# mb_01.net
KiCad netlist of a schematic drawn in EAGLE
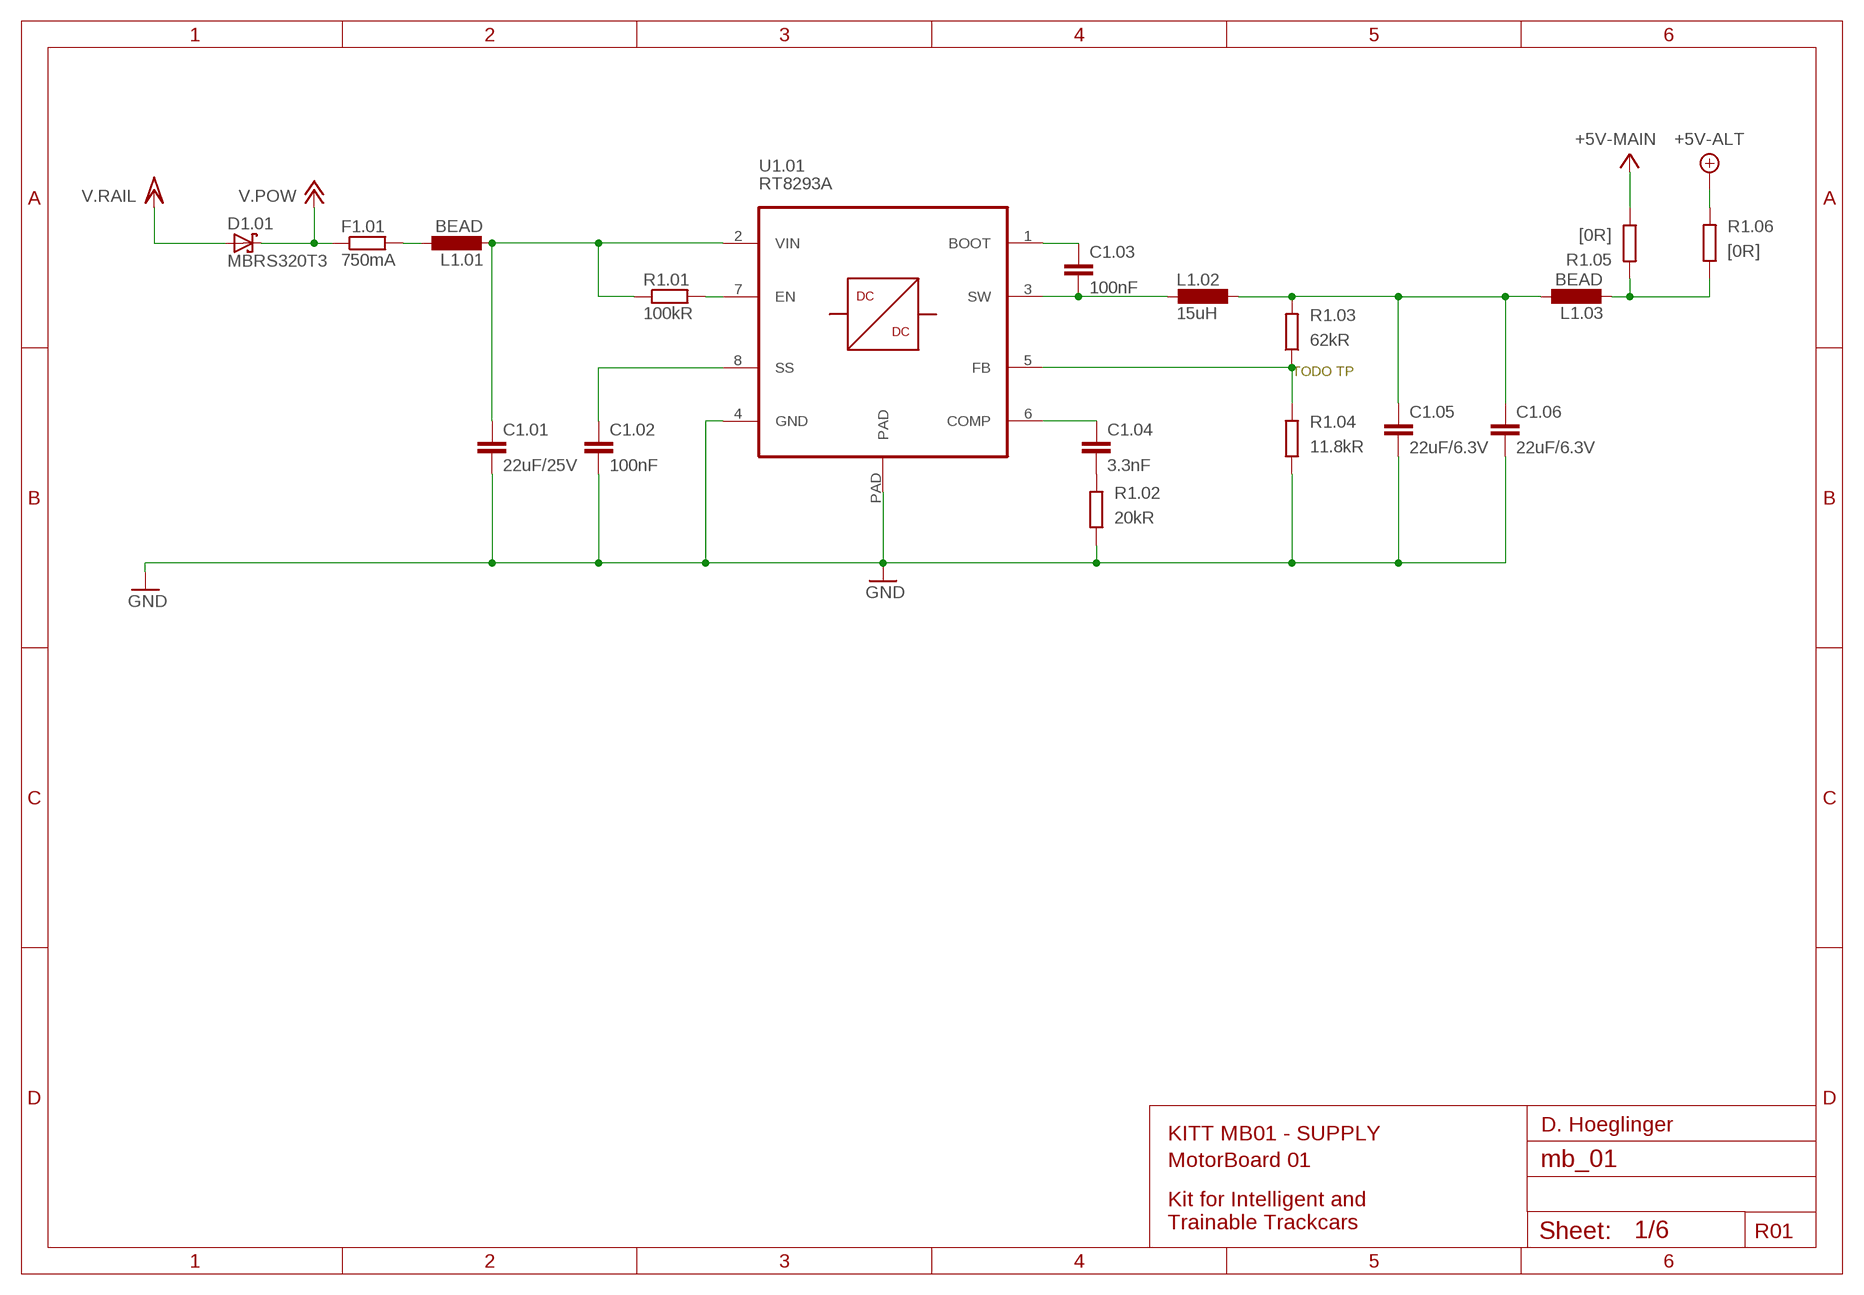
[diagram p0: schematic, sheet 1]
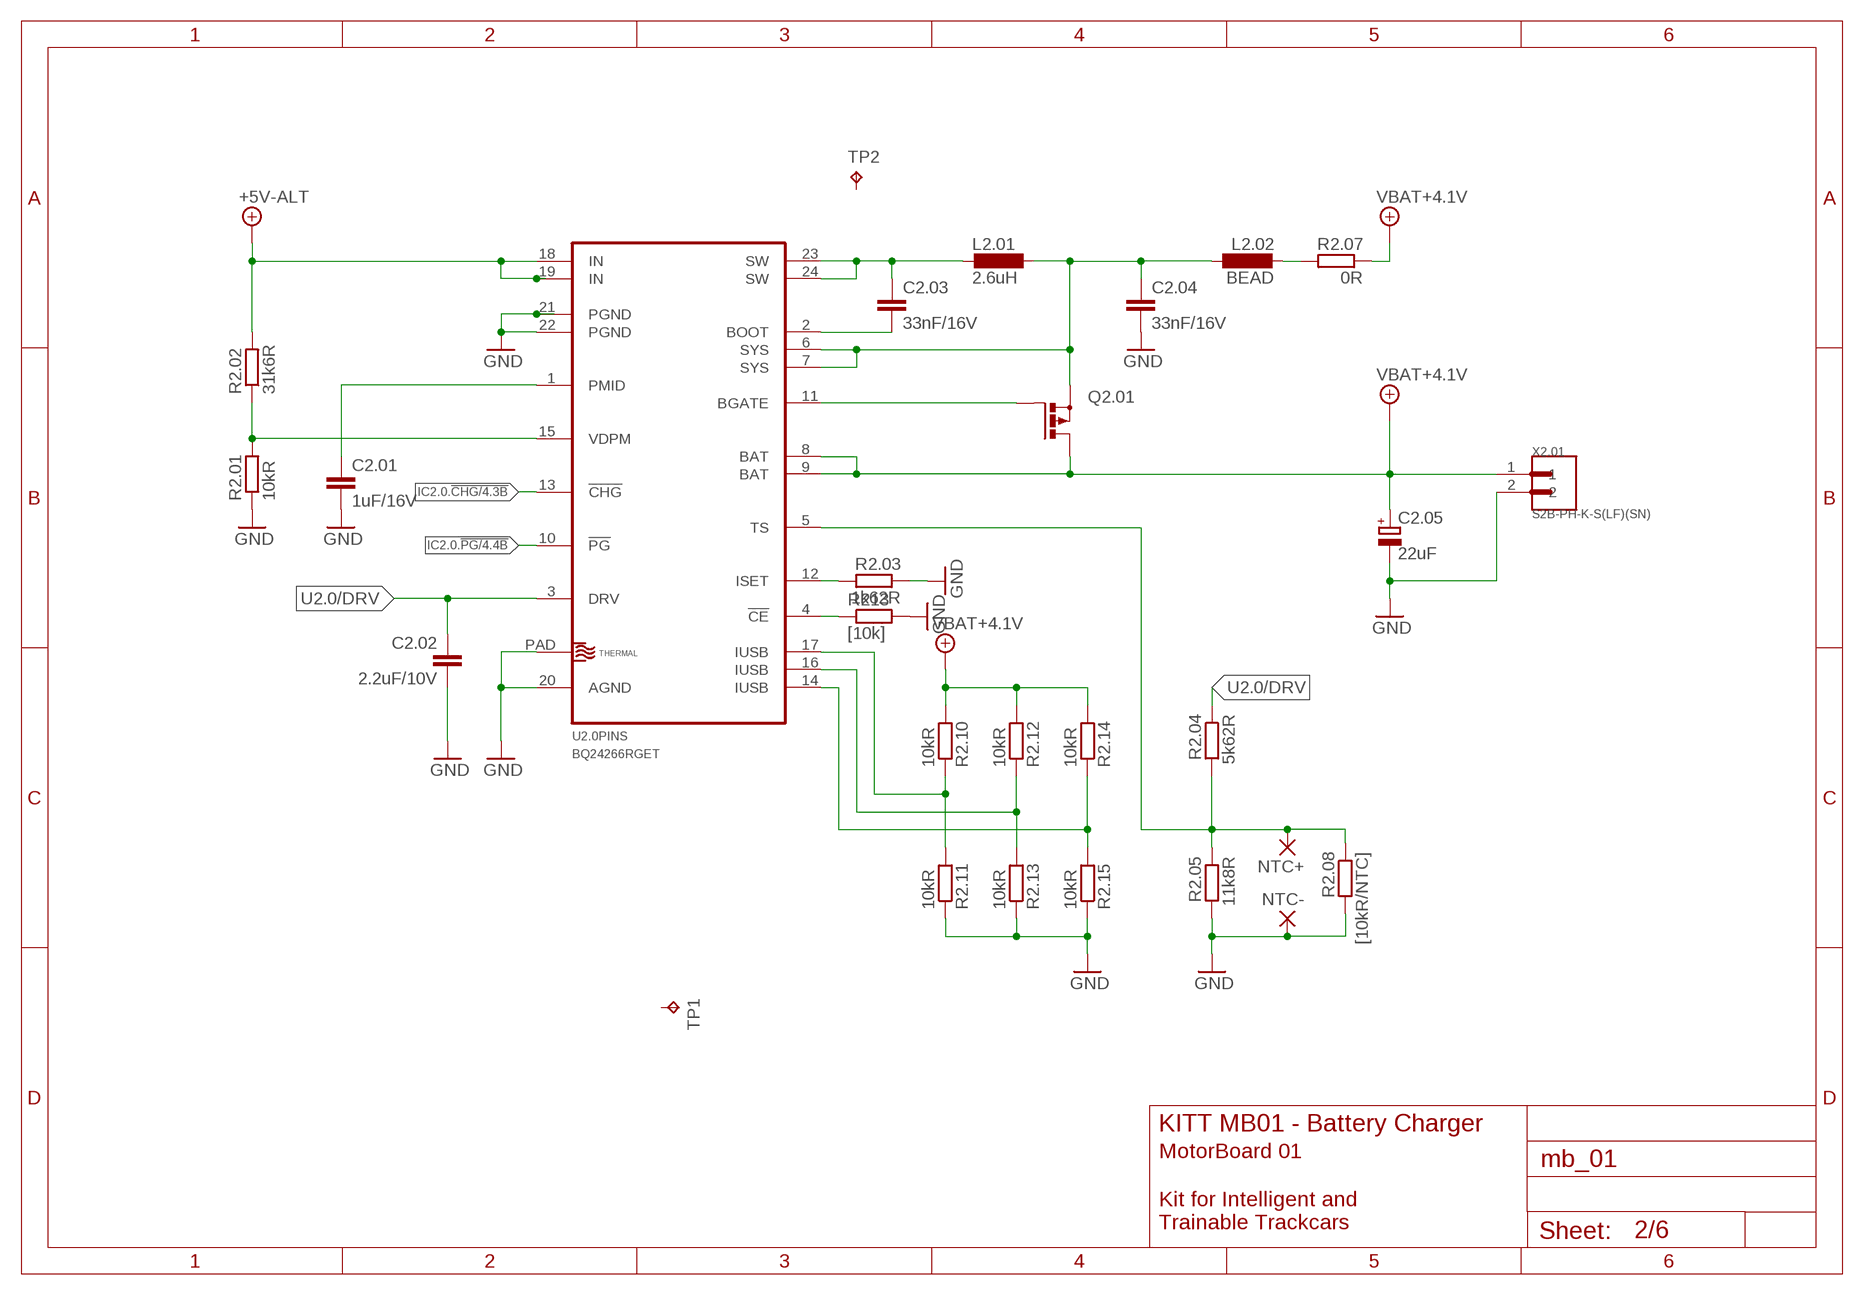
[diagram p1: schematic, sheet 2]
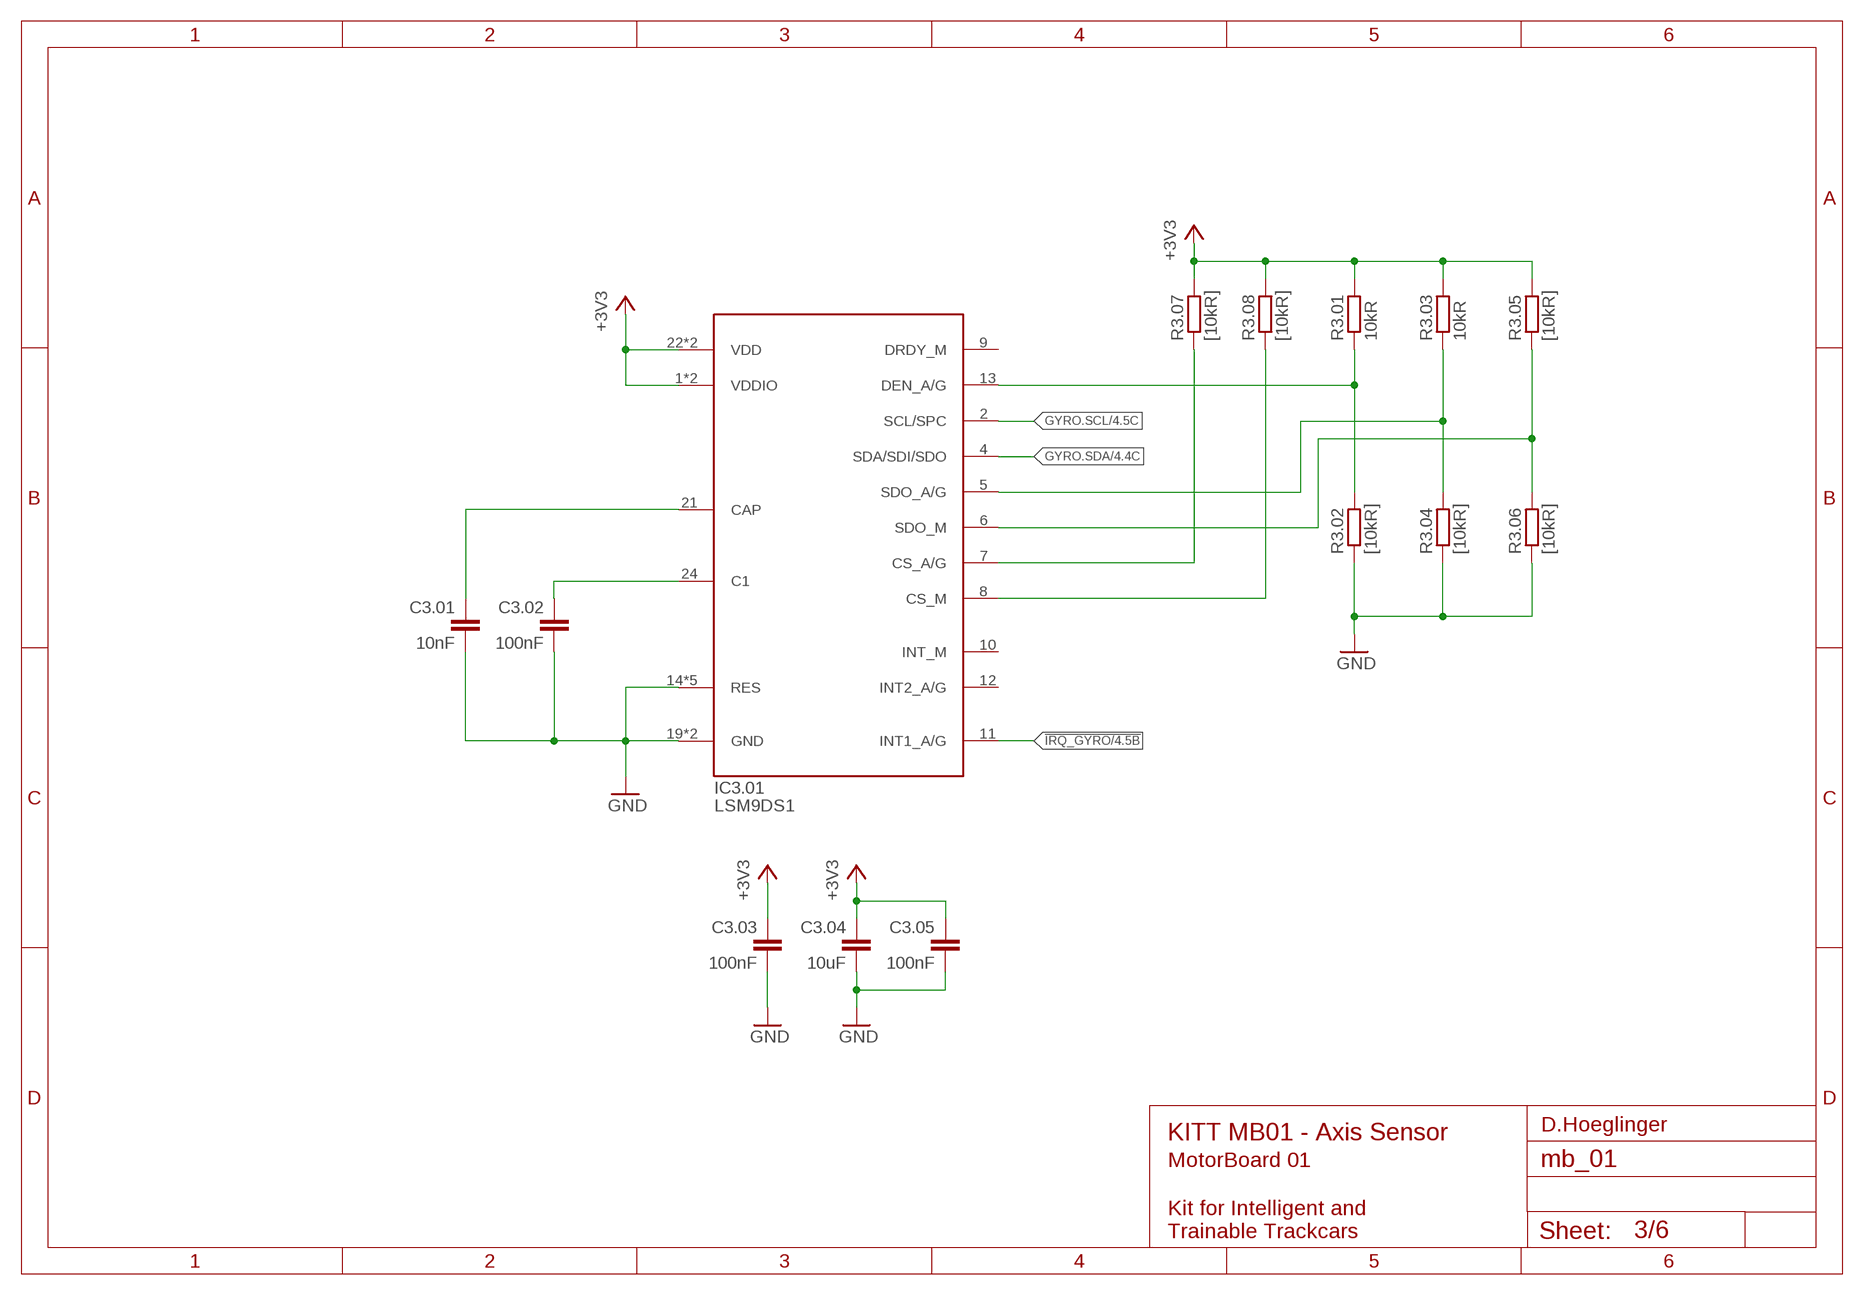
[diagram p2: schematic, sheet 3]
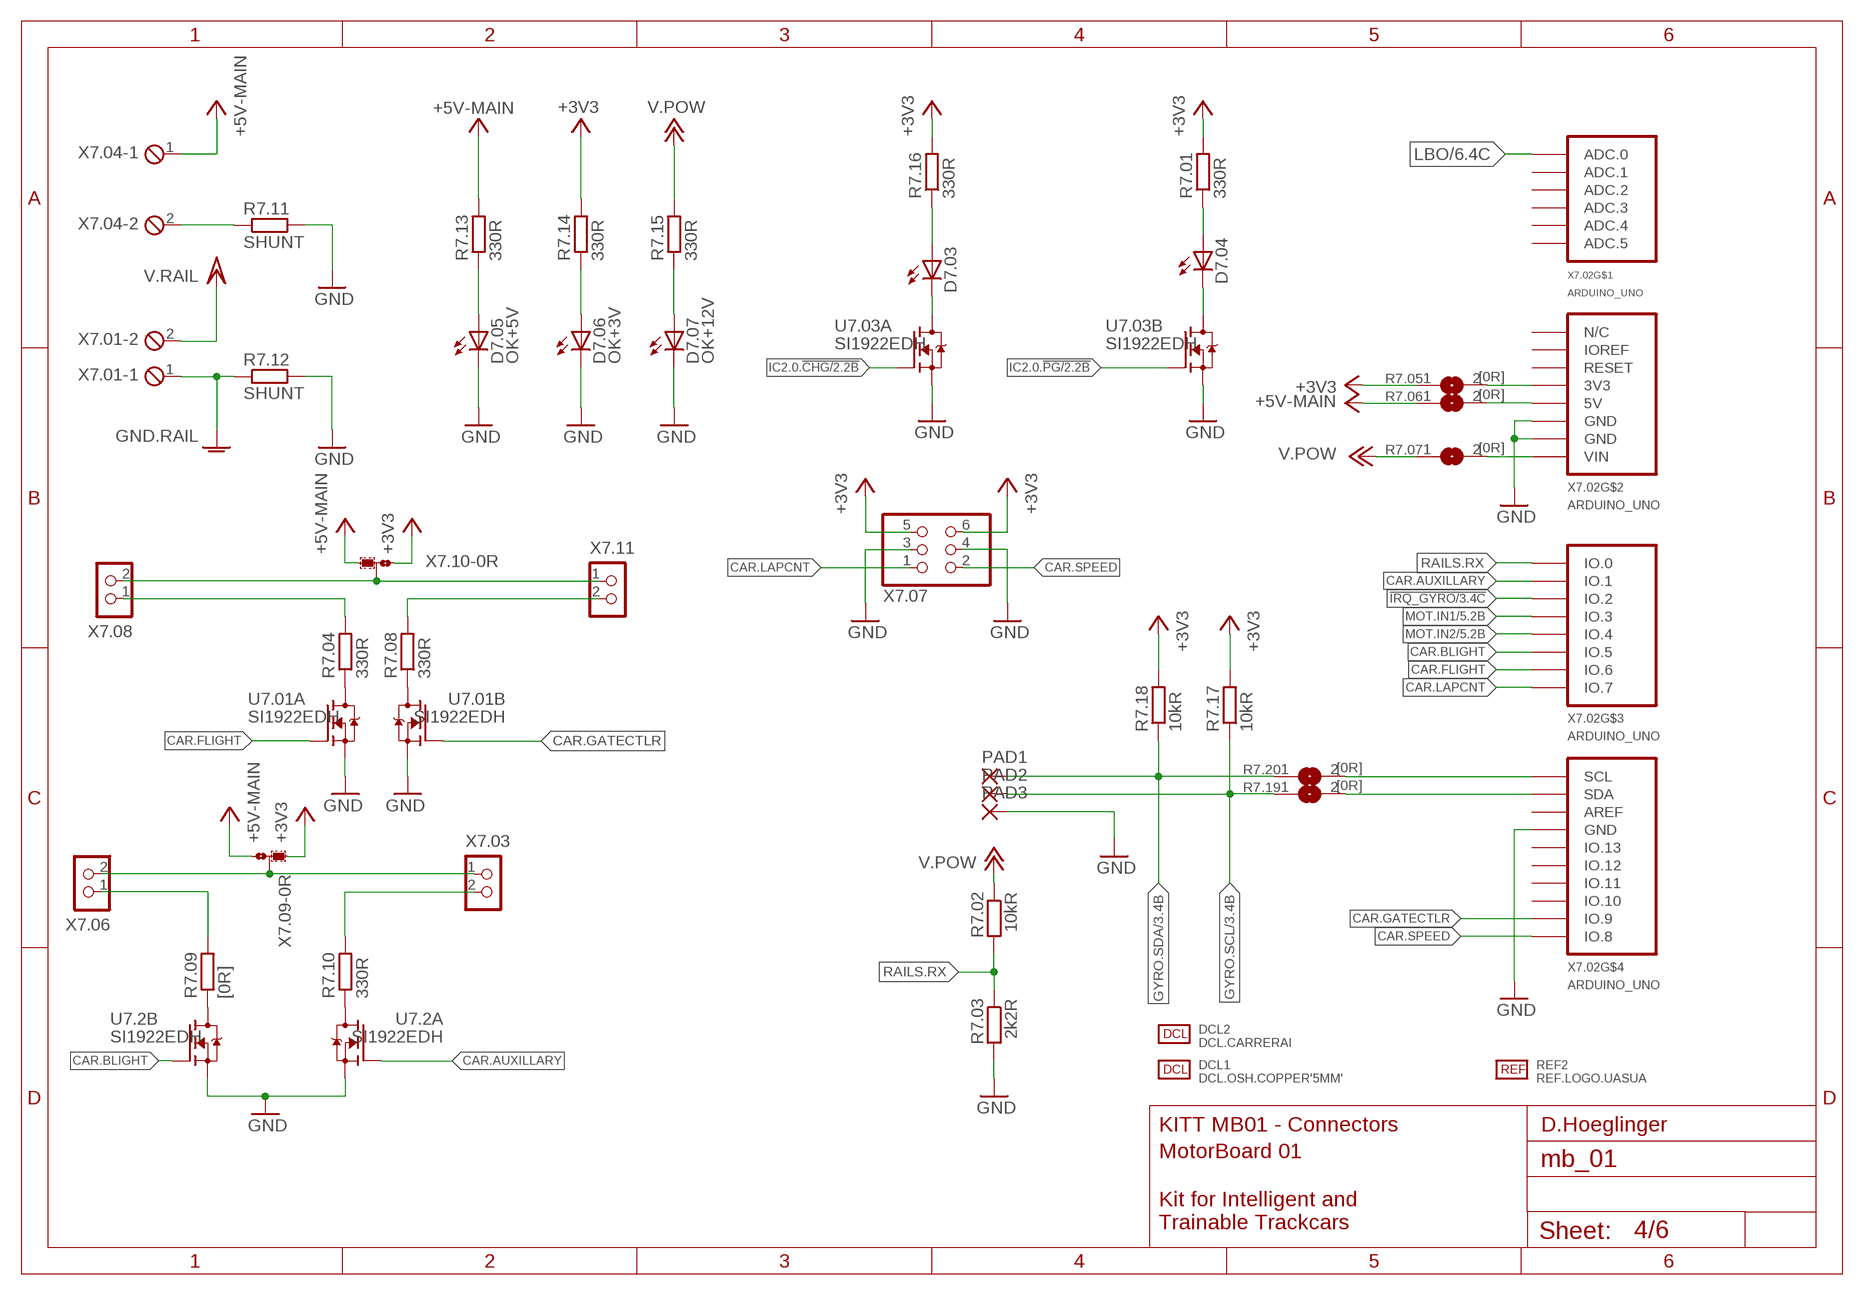
[diagram p3: schematic, sheet 4]
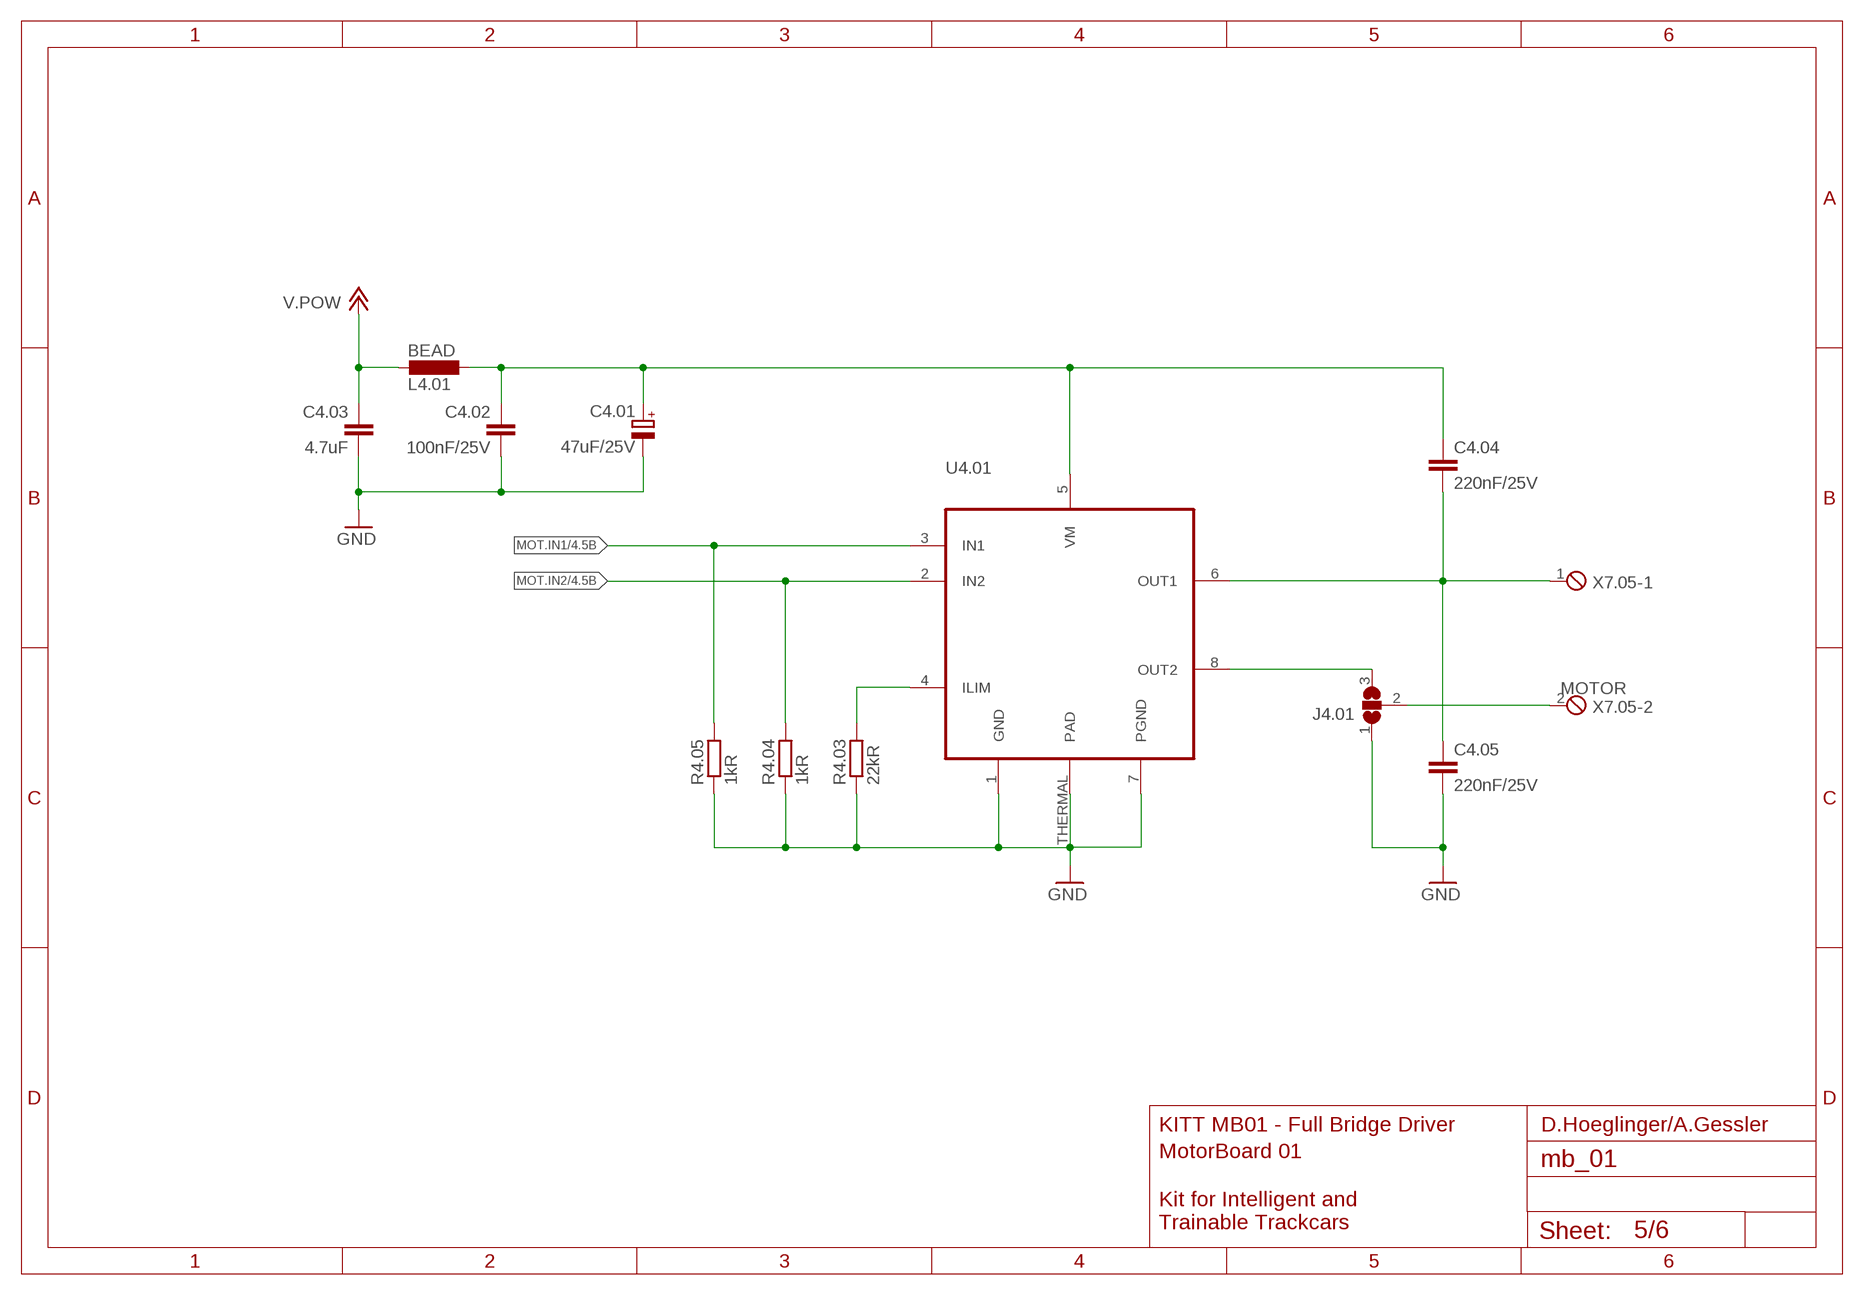
[diagram p4: schematic, sheet 5]
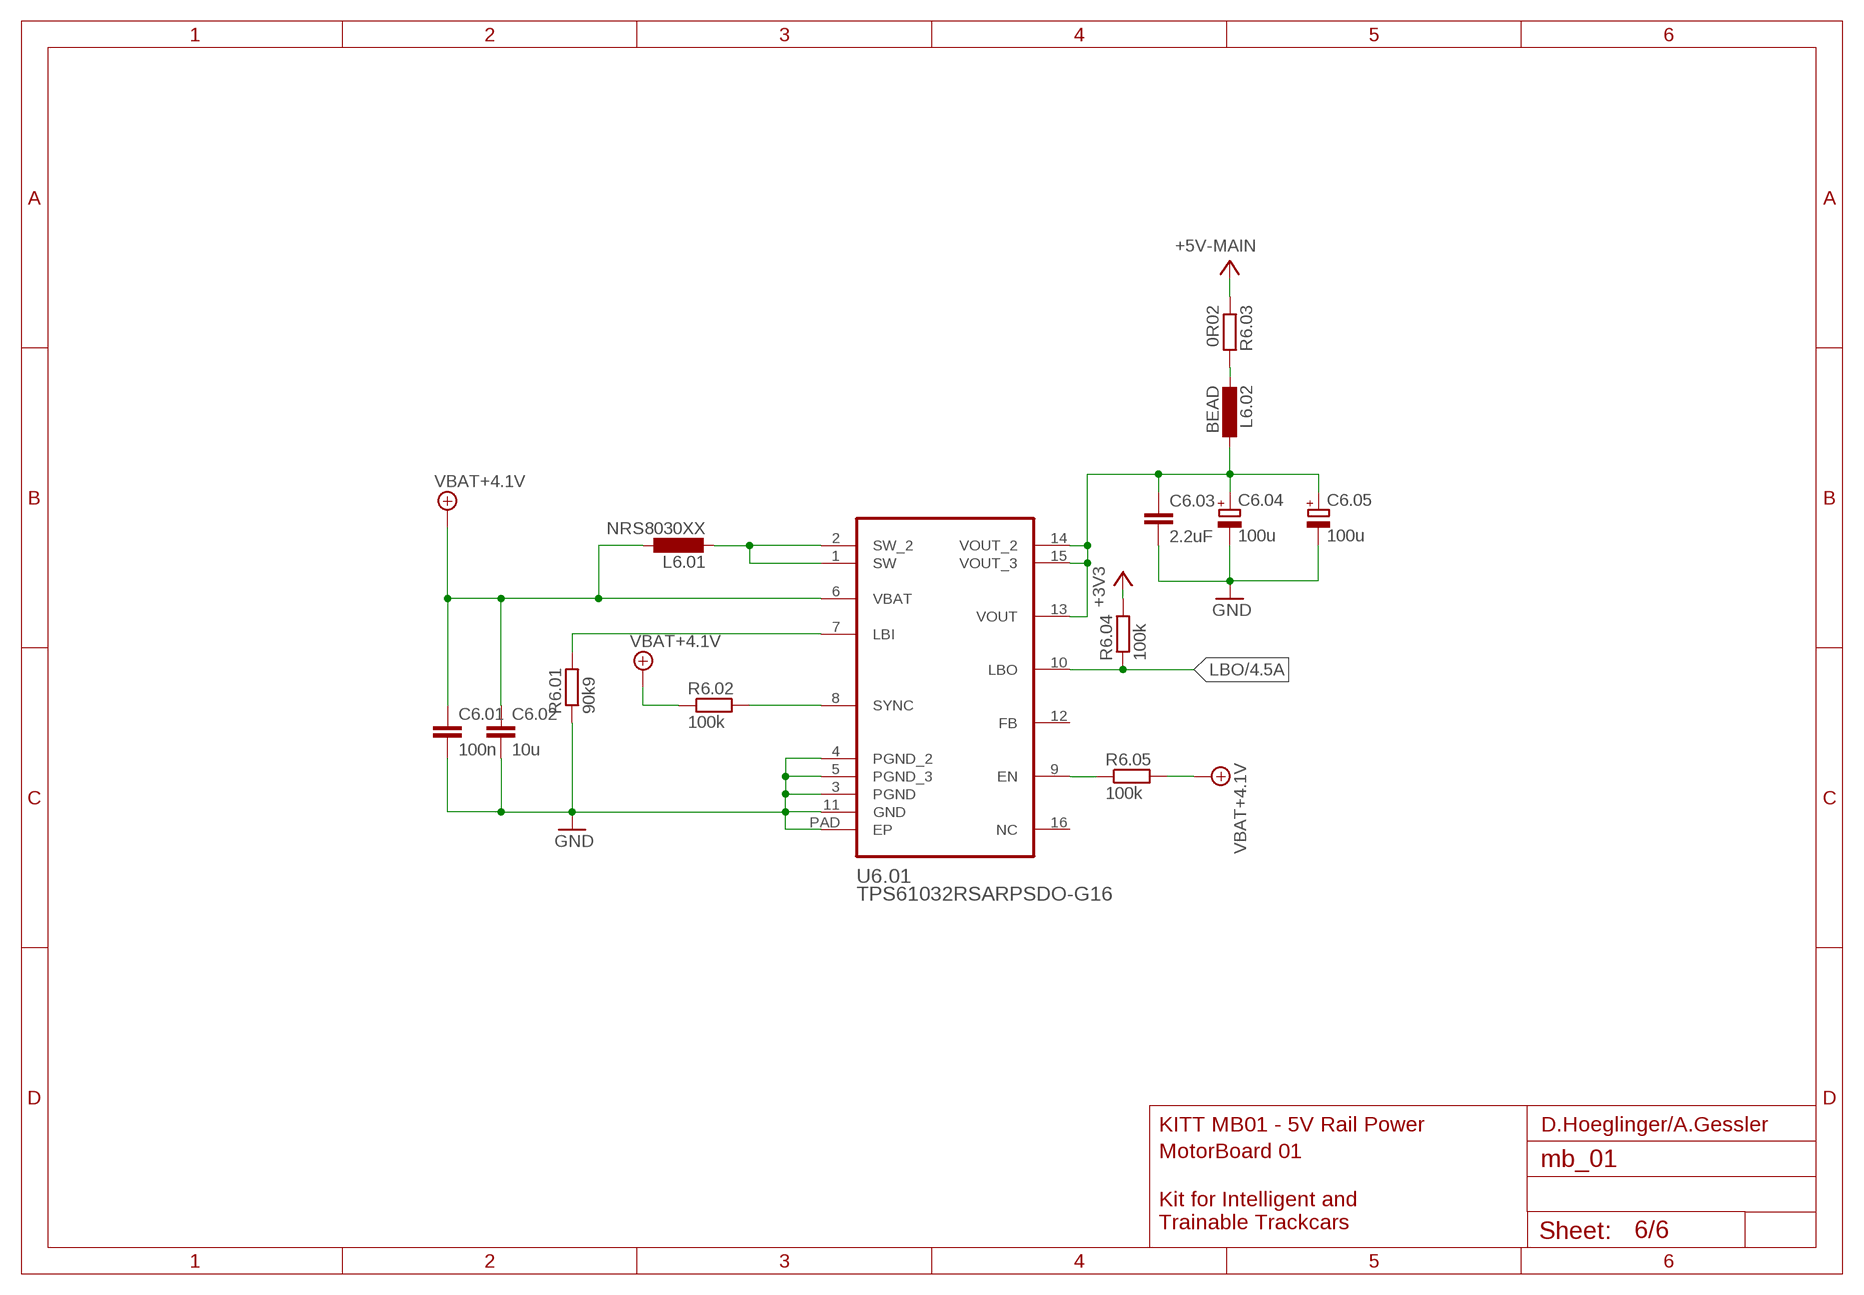
[diagram p5: schematic, sheet 6]

(export (version "E")
  (design (tool "Eeschema 10.0.6"))
  (components
    (comp (ref "C6.01")
      (value "100n")
      (footprint "eagle-import:C0402")
      (libsource (lib "eagle-import") (part "C-EUC0402"))
    )
    (comp (ref "C6.02")
      (value "10u")
      (footprint "eagle-import:C0603")
      (libsource (lib "eagle-import") (part "C-EUC0603"))
    )
    (comp (ref "C6.03")
      (value "2.2uF")
      (footprint "eagle-import:C0603")
      (libsource (lib "eagle-import") (part "C-EUC0603"))
    )
    (comp (ref "C6.04")
      (value "100u")
      (footprint "eagle-import:C-2312")
      (libsource (lib "eagle-import") (part "CPOL-29172312"))
    )
    (comp (ref "C6.05")
      (value "100u")
      (footprint "eagle-import:C-2312")
      (libsource (lib "eagle-import") (part "CPOL-29172312"))
    )
    (comp (ref "L6.01")
      (value "NRS8030XX")
      (footprint "eagle-import:TAIYO-YUDEN.NRS8030T4R7MJGJ")
      (libsource (lib "eagle-import") (part "NRS8030XX"))
    )
    (comp (ref "L6.02")
      (value "BEAD")
      (footprint "eagle-import:L4516C")
      (libsource (lib "eagle-import") (part "L-EUL4516C"))
    )
    (comp (ref "R6.01")
      (value "90k9")
      (footprint "eagle-import:R0402")
      (libsource (lib "eagle-import") (part "R-EU_R0402"))
    )
    (comp (ref "R6.02")
      (value "100k")
      (footprint "eagle-import:R0402")
      (libsource (lib "eagle-import") (part "R-EU_R0402"))
    )
    (comp (ref "R6.03")
      (value "0R02")
      (footprint "eagle-import:R0805")
      (libsource (lib "eagle-import") (part "R-EU_R0805"))
    )
    (comp (ref "R6.04")
      (value "100k")
      (footprint "eagle-import:R0402")
      (libsource (lib "eagle-import") (part "R-EU_R0402"))
    )
    (comp (ref "R6.05")
      (value "100k")
      (footprint "eagle-import:R0402")
      (libsource (lib "eagle-import") (part "R-EU_R0402"))
    )
    (comp (ref "U6.01")
      (value "TPS61032RSARPSDO-G16")
      (footprint "eagle-import:R-PDSO-G16")
      (libsource (lib "eagle-import") (part "TPS61032RSARPSDO-G16"))
    )
    (comp (ref "D7.03")
      (value "LEDCHIPLED_1206")
      (footprint "eagle-import:CHIPLED_1206")
      (libsource (lib "eagle-import") (part "LEDCHIPLED_1206"))
    )
    (comp (ref "D7.04")
      (value "LEDCHIPLED_1206")
      (footprint "eagle-import:CHIPLED_1206")
      (libsource (lib "eagle-import") (part "LEDCHIPLED_1206"))
    )
    (comp (ref "D7.05")
      (value "OK+5V")
      (footprint "eagle-import:CHIPLED_1206")
      (libsource (lib "eagle-import") (part "LEDCHIPLED_1206"))
    )
    (comp (ref "D7.06")
      (value "OK+3V")
      (footprint "eagle-import:CHIPLED_1206")
      (libsource (lib "eagle-import") (part "LEDCHIPLED_1206"))
    )
    (comp (ref "D7.07")
      (value "OK+12V")
      (footprint "eagle-import:CHIPLED_1206")
      (libsource (lib "eagle-import") (part "LEDCHIPLED_1206"))
    )
    (comp (ref "DCL1")
      (value "DCL.OSH.COPPER'5MM'")
      (footprint "eagle-import:DCL.LOGO-OSH.5MM")
      (libsource (lib "eagle-import") (part "DCL.OSH.COPPER'5MM'"))
    )
    (comp (ref "DCL2")
      (value "DCL.CARRERAI")
      (footprint "eagle-import:DCL.LOGO-CARRERAI.W30MM")
      (libsource (lib "eagle-import") (part "DCL.CARRERAI"))
    )
    (comp (ref "PAD1")
      (value "SMD2")
      (footprint "eagle-import:SMD1,27-2,54")
      (libsource (lib "eagle-import") (part "SMD2"))
    )
    (comp (ref "PAD2")
      (value "SMD2")
      (footprint "eagle-import:SMD1,27-2,54")
      (libsource (lib "eagle-import") (part "SMD2"))
    )
    (comp (ref "PAD3")
      (value "SMD2")
      (footprint "eagle-import:SMD1,27-2,54")
      (libsource (lib "eagle-import") (part "SMD2"))
    )
    (comp (ref "R7.01")
      (value "330R")
      (footprint "eagle-import:R0603")
      (libsource (lib "eagle-import") (part "R-EU_R0603"))
    )
    (comp (ref "R7.02")
      (value "10kR")
      (footprint "eagle-import:M0805")
      (libsource (lib "eagle-import") (part "R-EU_M0805"))
    )
    (comp (ref "R7.03")
      (value "2k2R")
      (footprint "eagle-import:M0805")
      (libsource (lib "eagle-import") (part "R-EU_M0805"))
    )
    (comp (ref "R7.04")
      (value "330R")
      (footprint "eagle-import:R0603")
      (libsource (lib "eagle-import") (part "R-EU_R0603"))
    )
    (comp (ref "R7.05")
      (value "[0R]")
      (footprint "eagle-import:SJ")
      (libsource (lib "eagle-import") (part "SJ"))
    )
    (comp (ref "R7.06")
      (value "[0R]")
      (footprint "eagle-import:SJ")
      (libsource (lib "eagle-import") (part "SJ"))
    )
    (comp (ref "R7.07")
      (value "[0R]")
      (footprint "eagle-import:SJ")
      (libsource (lib "eagle-import") (part "SJ"))
    )
    (comp (ref "R7.08")
      (value "330R")
      (footprint "eagle-import:R0603")
      (libsource (lib "eagle-import") (part "R-EU_R0603"))
    )
    (comp (ref "R7.09")
      (value "[0R]")
      (footprint "eagle-import:R0603")
      (libsource (lib "eagle-import") (part "R-EU_R0603"))
    )
    (comp (ref "R7.10")
      (value "330R")
      (footprint "eagle-import:R0603")
      (libsource (lib "eagle-import") (part "R-EU_R0603"))
    )
    (comp (ref "R7.11")
      (value "SHUNT")
      (footprint "eagle-import:R1206")
      (libsource (lib "eagle-import") (part "R-EU_R1206"))
    )
    (comp (ref "R7.12")
      (value "SHUNT")
      (footprint "eagle-import:R1206")
      (libsource (lib "eagle-import") (part "R-EU_R1206"))
    )
    (comp (ref "R7.13")
      (value "330R")
      (footprint "eagle-import:R0603")
      (libsource (lib "eagle-import") (part "R-EU_R0603"))
    )
    (comp (ref "R7.14")
      (value "330R")
      (footprint "eagle-import:R0603")
      (libsource (lib "eagle-import") (part "R-EU_R0603"))
    )
    (comp (ref "R7.15")
      (value "330R")
      (footprint "eagle-import:R0603")
      (libsource (lib "eagle-import") (part "R-EU_R0603"))
    )
    (comp (ref "R7.16")
      (value "330R")
      (footprint "eagle-import:R0603")
      (libsource (lib "eagle-import") (part "R-EU_R0603"))
    )
    (comp (ref "R7.17")
      (value "10kR")
      (footprint "eagle-import:R0402")
      (libsource (lib "eagle-import") (part "R-EU_R0402"))
    )
    (comp (ref "R7.18")
      (value "10kR")
      (footprint "eagle-import:R0402")
      (libsource (lib "eagle-import") (part "R-EU_R0402"))
    )
    (comp (ref "R7.19")
      (value "[0R]")
      (footprint "eagle-import:SJ")
      (libsource (lib "eagle-import") (part "SJ"))
    )
    (comp (ref "R7.20")
      (value "[0R]")
      (footprint "eagle-import:SJ")
      (libsource (lib "eagle-import") (part "SJ"))
    )
    (comp (ref "REF2")
      (value "REF.LOGO.UASUA")
      (footprint "eagle-import:REF_LOGO_UASUA")
      (libsource (lib "eagle-import") (part "REF.LOGO.UASUA"))
    )
    (comp (ref "U7.01")
      (value "SI1922EDH")
      (footprint "eagle-import:SC70-6")
      (libsource (lib "eagle-import") (part "SI1922EDH"))
    )
    (comp (ref "U7.2")
      (value "SI1922EDH")
      (footprint "eagle-import:SC70-6")
      (libsource (lib "eagle-import") (part "SI1922EDH"))
    )
    (comp (ref "U7.03")
      (value "SI1922EDH")
      (footprint "eagle-import:SC70-6")
      (libsource (lib "eagle-import") (part "SI1922EDH"))
    )
    (comp (ref "X7.01")
      (value "MPT2")
      (footprint "eagle-import:2POL254")
      (libsource (lib "eagle-import") (part "MPT2"))
    )
    (comp (ref "X7.02")
      (value "ARDUINO_UNO")
      (footprint "eagle-import:AU_PINS")
      (libsource (lib "eagle-import") (part "ARDUINO_UNO"))
    )
    (comp (ref "X7.03")
      (value "CON_HEADER_1X02")
      (footprint "eagle-import:M1X2_MALE_RIGHT_ANGLED_SMD")
      (libsource (lib "eagle-import") (part "CON_HEADER_1X02"))
    )
    (comp (ref "X7.04")
      (value "MPT2")
      (footprint "eagle-import:2POL254")
      (libsource (lib "eagle-import") (part "MPT2"))
    )
    (comp (ref "X7.06")
      (value "CON_HEADER_1X02")
      (footprint "eagle-import:M1X2_MALE_RIGHT_ANGLED_SMD")
      (libsource (lib "eagle-import") (part "CON_HEADER_1X02"))
    )
    (comp (ref "X7.07")
      (value "PINHD-2X3/90")
      (footprint "eagle-import:2X03_90")
      (libsource (lib "eagle-import") (part "PINHD-2X3/90"))
    )
    (comp (ref "X7.08")
      (value "CON_HEADER_1X02")
      (footprint "eagle-import:M1X2_MALE_RIGHT_ANGLED_SMD")
      (libsource (lib "eagle-import") (part "CON_HEADER_1X02"))
    )
    (comp (ref "X7.09")
      (value "0R-JUMPA")
      (footprint "eagle-import:A0R-JMP")
      (libsource (lib "eagle-import") (part "0R-JUMPA"))
    )
    (comp (ref "X7.10")
      (value "0R-JUMPA")
      (footprint "eagle-import:A0R-JMP")
      (libsource (lib "eagle-import") (part "0R-JUMPA"))
    )
    (comp (ref "X7.11")
      (value "CON_HEADER_1X02")
      (footprint "eagle-import:M1X2_MALE_RIGHT_ANGLED_SMD")
      (libsource (lib "eagle-import") (part "CON_HEADER_1X02"))
    )
    (comp (ref "C3.01")
      (value "10nF")
      (footprint "eagle-import:C0603")
      (libsource (lib "eagle-import") (part "C-EUC0603"))
    )
    (comp (ref "C3.02")
      (value "100nF")
      (footprint "eagle-import:C0402")
      (libsource (lib "eagle-import") (part "C-EUC0402"))
    )
    (comp (ref "C3.03")
      (value "100nF")
      (footprint "eagle-import:C0402")
      (libsource (lib "eagle-import") (part "C-EUC0402"))
    )
    (comp (ref "C3.04")
      (value "10uF")
      (footprint "eagle-import:C0603K")
      (libsource (lib "eagle-import") (part "resistor_C-EUC0603K"))
    )
    (comp (ref "C3.05")
      (value "100nF")
      (footprint "eagle-import:C0402")
      (libsource (lib "eagle-import") (part "C-EUC0402"))
    )
    (comp (ref "IC3.01")
      (value "LSM9DS1")
      (footprint "eagle-import:LGA-24")
      (fields (field (name "MF") "STMicroelectronics"))
      (libsource (lib "eagle-import") (part "LSM9DS1"))
    )
    (comp (ref "R3.01")
      (value "10kR")
      (footprint "eagle-import:R0402")
      (libsource (lib "eagle-import") (part "R-EU_R0402"))
    )
    (comp (ref "R3.02")
      (value "[10kR]")
      (footprint "eagle-import:R0402")
      (libsource (lib "eagle-import") (part "R-EU_R0402"))
    )
    (comp (ref "R3.03")
      (value "10kR")
      (footprint "eagle-import:R0402")
      (libsource (lib "eagle-import") (part "R-EU_R0402"))
    )
    (comp (ref "R3.04")
      (value "[10kR]")
      (footprint "eagle-import:R0402")
      (libsource (lib "eagle-import") (part "R-EU_R0402"))
    )
    (comp (ref "R3.05")
      (value "[10kR]")
      (footprint "eagle-import:R0402")
      (libsource (lib "eagle-import") (part "R-EU_R0402"))
    )
    (comp (ref "R3.06")
      (value "[10kR]")
      (footprint "eagle-import:R0402")
      (libsource (lib "eagle-import") (part "R-EU_R0402"))
    )
    (comp (ref "R3.07")
      (value "[10kR]")
      (footprint "eagle-import:R0402")
      (libsource (lib "eagle-import") (part "R-EU_R0402"))
    )
    (comp (ref "R3.08")
      (value "[10kR]")
      (footprint "eagle-import:R0402")
      (libsource (lib "eagle-import") (part "R-EU_R0402"))
    )
    (comp (ref "C2.01")
      (value "1uF/16V")
      (footprint "eagle-import:C0805")
      (libsource (lib "eagle-import") (part "C-EUC0805"))
    )
    (comp (ref "C2.02")
      (value "2.2uF/10V")
      (footprint "eagle-import:C0603K")
      (libsource (lib "eagle-import") (part "C-EUC0603K"))
    )
    (comp (ref "C2.03")
      (value "33nF/16V")
      (footprint "eagle-import:C0603")
      (libsource (lib "eagle-import") (part "C-EUC0603"))
    )
    (comp (ref "C2.04")
      (value "33nF/16V")
      (footprint "eagle-import:C0805")
      (libsource (lib "eagle-import") (part "C-EUC0805"))
    )
    (comp (ref "C2.05")
      (value "22uF")
      (footprint "eagle-import:A_3216-18R")
      (libsource (lib "eagle-import") (part "CPOL-EUA/3216-18R"))
    )
    (comp (ref "L2.01")
      (value "2.6uH")
      (footprint "eagle-import:TAIYO-YUDEN.NRS8030T4R7MJGJ")
      (libsource (lib "eagle-import") (part "NRS8030XX"))
    )
    (comp (ref "L2.02")
      (value "BEAD")
      (footprint "eagle-import:L4516C")
      (libsource (lib "eagle-import") (part "L-EUL4516C"))
    )
    (comp (ref "NTC+")
      (value "SMD2")
      (footprint "eagle-import:SMD1,27-2,54")
      (libsource (lib "eagle-import") (part "SMD2"))
    )
    (comp (ref "NTC-")
      (value "SMD2")
      (footprint "eagle-import:SMD1,27-2,54")
      (libsource (lib "eagle-import") (part "SMD2"))
    )
    (comp (ref "Q2.01")
      (value "P-MOSFET-SO8")
      (footprint "eagle-import:SO-08")
      (libsource (lib "eagle-import") (part "P-MOSFET-SO8"))
    )
    (comp (ref "R2.01")
      (value "10kR")
      (footprint "eagle-import:R0402")
      (libsource (lib "eagle-import") (part "R-EU_R0402"))
    )
    (comp (ref "R2.02")
      (value "31k6R")
      (footprint "eagle-import:R0402")
      (libsource (lib "eagle-import") (part "R-EU_R0402"))
    )
    (comp (ref "R2.03")
      (value "1k62R")
      (footprint "eagle-import:R0402")
      (libsource (lib "eagle-import") (part "R-EU_R0402"))
    )
    (comp (ref "R2.04")
      (value "5k62R")
      (footprint "eagle-import:R0402")
      (libsource (lib "eagle-import") (part "R-EU_R0402"))
    )
    (comp (ref "R2.05")
      (value "11k8R")
      (footprint "eagle-import:R0402")
      (libsource (lib "eagle-import") (part "R-EU_R0402"))
    )
    (comp (ref "R2.07")
      (value "0R")
      (footprint "eagle-import:R0402")
      (libsource (lib "eagle-import") (part "R-EU_R0402"))
    )
    (comp (ref "R2.08")
      (value "[10kR/NTC]")
      (footprint "eagle-import:R0402")
      (libsource (lib "eagle-import") (part "R-EU_R0402"))
    )
    (comp (ref "R2.10")
      (value "10kR")
      (footprint "eagle-import:R0402")
      (libsource (lib "eagle-import") (part "R-EU_R0402"))
    )
    (comp (ref "R2.11")
      (value "10kR")
      (footprint "eagle-import:R0402")
      (libsource (lib "eagle-import") (part "R-EU_R0402"))
    )
    (comp (ref "R2.12")
      (value "10kR")
      (footprint "eagle-import:R0402")
      (libsource (lib "eagle-import") (part "R-EU_R0402"))
    )
    (comp (ref "R2.13")
      (value "10kR")
      (footprint "eagle-import:R0402")
      (libsource (lib "eagle-import") (part "R-EU_R0402"))
    )
    (comp (ref "R2.14")
      (value "10kR")
      (footprint "eagle-import:R0402")
      (libsource (lib "eagle-import") (part "R-EU_R0402"))
    )
    (comp (ref "R2.15")
      (value "10kR")
      (footprint "eagle-import:R0402")
      (libsource (lib "eagle-import") (part "R-EU_R0402"))
    )
    (comp (ref "R213")
      (value "[10k]")
      (footprint "eagle-import:R01005")
      (libsource (lib "eagle-import") (part "R-EU_01005"))
    )
    (comp (ref "TP1")
      (value "TPTP07R")
      (footprint "eagle-import:TP07R")
      (libsource (lib "eagle-import") (part "TPTP07R"))
    )
    (comp (ref "TP2")
      (value "TPTP07R")
      (footprint "eagle-import:TP07R")
      (libsource (lib "eagle-import") (part "TPTP07R"))
    )
    (comp (ref "U2.0")
      (value "BQ24266RGET")
      (footprint "eagle-import:VQFN-24")
      (libsource (lib "eagle-import") (part "BQ24266RGET"))
    )
    (comp (ref "X2.01")
      (value "S2B-PH-K-S(LF)(SN)")
      (footprint "eagle-import:JST_S2B-PH-K-S(LF)(SN)")
      (fields (field (name "MF") "JST"))
      (libsource (lib "eagle-import") (part "S2B-PH-K-S(LF)(SN)"))
    )
    (comp (ref "C4.01")
      (value "47uF/25V")
      (footprint "eagle-import:C_6032-28R")
      (libsource (lib "eagle-import") (part "CPOL-EUC/6032-28R"))
    )
    (comp (ref "C4.02")
      (value "100nF/25V")
      (footprint "eagle-import:C0603K")
      (libsource (lib "eagle-import") (part "resistor_C-EUC0603K"))
    )
    (comp (ref "C4.03")
      (value "4.7uF")
      (footprint "eagle-import:C0805K")
      (libsource (lib "eagle-import") (part "resistor_C-EUC0805K"))
    )
    (comp (ref "C4.04")
      (value "220nF/25V")
      (footprint "eagle-import:C0603K")
      (libsource (lib "eagle-import") (part "C-EUC0603K"))
    )
    (comp (ref "C4.05")
      (value "220nF/25V")
      (footprint "eagle-import:C0603K")
      (libsource (lib "eagle-import") (part "C-EUC0603K"))
    )
    (comp (ref "J4.01")
      (value "SJ2W")
      (footprint "eagle-import:SJ_2")
      (libsource (lib "eagle-import") (part "SJ2W"))
    )
    (comp (ref "L4.01")
      (value "BEAD")
      (footprint "eagle-import:L4516C")
      (libsource (lib "eagle-import") (part "L-EUL4516C"))
    )
    (comp (ref "R4.03")
      (value "22kR")
      (footprint "eagle-import:R0402")
      (libsource (lib "eagle-import") (part "resistor_R-EU_R0402"))
    )
    (comp (ref "R4.04")
      (value "1kR")
      (footprint "eagle-import:R0402")
      (libsource (lib "eagle-import") (part "resistor_R-EU_R0402"))
    )
    (comp (ref "R4.05")
      (value "1kR")
      (footprint "eagle-import:R0402")
      (libsource (lib "eagle-import") (part "resistor_R-EU_R0402"))
    )
    (comp (ref "U4.01")
      (value "DRV8871")
      (footprint "eagle-import:HSOP8")
      (libsource (lib "eagle-import") (part "DRV8871"))
    )
    (comp (ref "X7.05")
      (value "MOTOR")
      (footprint "eagle-import:2POL254")
      (libsource (lib "eagle-import") (part "MPT2"))
    )
    (comp (ref "C1.01")
      (value "22uF/25V")
      (footprint "eagle-import:C1210K")
      (libsource (lib "eagle-import") (part "C-EUC1210K"))
    )
    (comp (ref "C1.02")
      (value "100nF")
      (footprint "eagle-import:C0402K")
      (libsource (lib "eagle-import") (part "C-EUC0402K"))
    )
    (comp (ref "C1.03")
      (value "100nF")
      (footprint "eagle-import:C0402K")
      (libsource (lib "eagle-import") (part "C-EUC0402K"))
    )
    (comp (ref "C1.04")
      (value "3.3nF")
      (footprint "eagle-import:C0402K")
      (libsource (lib "eagle-import") (part "C-EUC0402K"))
    )
    (comp (ref "C1.05")
      (value "22uF/6.3V")
      (footprint "eagle-import:C1206K")
      (libsource (lib "eagle-import") (part "C-EUC1206K"))
    )
    (comp (ref "C1.06")
      (value "22uF/6.3V")
      (footprint "eagle-import:C1206K")
      (libsource (lib "eagle-import") (part "C-EUC1206K"))
    )
    (comp (ref "D1.01")
      (value "MBRS320T3")
      (footprint "eagle-import:SMC")
      (libsource (lib "eagle-import") (part "MBRS30T32"))
    )
    (comp (ref "F1.01")
      (value "750mA")
      (footprint "eagle-import:R1210")
      (libsource (lib "eagle-import") (part "R-EU_R1210"))
    )
    (comp (ref "L1.01")
      (value "BEAD")
      (footprint "eagle-import:L4516C")
      (libsource (lib "eagle-import") (part "L-EUL4516C"))
    )
    (comp (ref "L1.02")
      (value "15uH")
      (footprint "eagle-import:TAIYO-YUDEN.NRS8030T4R7MJGJ")
      (libsource (lib "eagle-import") (part "NRS8030XX"))
    )
    (comp (ref "L1.03")
      (value "BEAD")
      (footprint "eagle-import:L4516C")
      (libsource (lib "eagle-import") (part "L-EUL4516C"))
    )
    (comp (ref "R1.01")
      (value "100kR")
      (footprint "eagle-import:R0402")
      (libsource (lib "eagle-import") (part "R-EU_R0402"))
    )
    (comp (ref "R1.02")
      (value "20kR")
      (footprint "eagle-import:R0402")
      (libsource (lib "eagle-import") (part "R-EU_R0402"))
    )
    (comp (ref "R1.03")
      (value "62kR")
      (footprint "eagle-import:R0402")
      (libsource (lib "eagle-import") (part "R-EU_R0402"))
    )
    (comp (ref "R1.04")
      (value "11.8kR")
      (footprint "eagle-import:R0402")
      (libsource (lib "eagle-import") (part "R-EU_R0402"))
    )
    (comp (ref "R1.05")
      (value "[0R]")
      (footprint "eagle-import:R0402")
      (libsource (lib "eagle-import") (part "R-EU_R0402"))
    )
    (comp (ref "R1.06")
      (value "[0R]")
      (footprint "eagle-import:R0402")
      (libsource (lib "eagle-import") (part "R-EU_R0402"))
    )
    (comp (ref "U1.01")
      (value "RT8293A")
      (footprint "eagle-import:SOIC-8-PAD")
      (libsource (lib "eagle-import") (part "RT8293A"))
    )
  )
  (nets
    (net (code "1") (name "+3V3") (class "Default")
      (node (ref "C3.03") (pin "1") (pinfunction "1_1") (pintype "passive"))
      (node (ref "C3.04") (pin "1") (pinfunction "1_1") (pintype "passive"))
      (node (ref "C3.05") (pin "1") (pinfunction "1_1") (pintype "passive"))
      (node (ref "IC3.01") (pin "1") (pinfunction "VDDIO_1") (pintype "bidirectional"))
      (node (ref "IC3.01") (pin "22") (pinfunction "VDD_22") (pintype "bidirectional"))
      (node (ref "IC3.01") (pin "23") (pinfunction "VDD_23") (pintype "bidirectional"))
      (node (ref "IC3.01") (pin "3") (pinfunction "VDDIO_3") (pintype "bidirectional"))
      (node (ref "R3.01") (pin "2") (pinfunction "2_2") (pintype "passive"))
      (node (ref "R3.03") (pin "2") (pinfunction "2_2") (pintype "passive"))
      (node (ref "R3.05") (pin "2") (pinfunction "2_2") (pintype "passive"))
      (node (ref "R3.07") (pin "2") (pinfunction "2_2") (pintype "passive"))
      (node (ref "R3.08") (pin "2") (pinfunction "2_2") (pintype "passive"))
      (node (ref "R6.04") (pin "2") (pinfunction "2_2") (pintype "passive"))
      (node (ref "R7.01") (pin "2") (pinfunction "2_2") (pintype "passive"))
      (node (ref "R7.05") (pin "1") (pinfunction "1_1") (pintype "passive"))
      (node (ref "R7.14") (pin "2") (pinfunction "2_2") (pintype "passive"))
      (node (ref "R7.16") (pin "2") (pinfunction "2_2") (pintype "passive"))
      (node (ref "R7.17") (pin "2") (pinfunction "2_2") (pintype "passive"))
      (node (ref "R7.18") (pin "2") (pinfunction "2_2") (pintype "passive"))
      (node (ref "X7.07") (pin "5") (pinfunction "5_5") (pintype "passive"))
      (node (ref "X7.07") (pin "6") (pinfunction "6_6") (pintype "passive"))
      (node (ref "X7.09") (pin "1") (pinfunction "1_1") (pintype "passive"))
      (node (ref "X7.10") (pin "1") (pinfunction "1_1") (pintype "passive"))
    )
    (net (code "2") (name "+4.1V") (class "Default")
      (node (ref "C2.05") (pin "+") (pinfunction "+_+") (pintype "passive"))
      (node (ref "C6.01") (pin "1") (pinfunction "1_1") (pintype "passive"))
      (node (ref "C6.02") (pin "1") (pinfunction "1_1") (pintype "passive"))
      (node (ref "L6.01") (pin "1") (pinfunction "1_1") (pintype "passive"))
      (node (ref "Q2.01") (pin "5") (pinfunction "D_5") (pintype "passive"))
      (node (ref "Q2.01") (pin "6") (pinfunction "D_6") (pintype "passive"))
      (node (ref "Q2.01") (pin "7") (pinfunction "D_7") (pintype "passive"))
      (node (ref "Q2.01") (pin "8") (pinfunction "D_8") (pintype "passive"))
      (node (ref "R2.07") (pin "1") (pinfunction "1_1") (pintype "passive"))
      (node (ref "R2.10") (pin "2") (pinfunction "2_2") (pintype "passive"))
      (node (ref "R2.12") (pin "2") (pinfunction "2_2") (pintype "passive"))
      (node (ref "R2.14") (pin "2") (pinfunction "2_2") (pintype "passive"))
      (node (ref "R6.02") (pin "1") (pinfunction "1_1") (pintype "passive"))
      (node (ref "R6.05") (pin "2") (pinfunction "2_2") (pintype "passive"))
      (node (ref "U2.0") (pin "8") (pinfunction "BAT_8") (pintype "bidirectional"))
      (node (ref "U2.0") (pin "9") (pinfunction "BAT_9") (pintype "bidirectional"))
      (node (ref "U6.01") (pin "6") (pinfunction "VBAT_6") (pintype "input"))
      (node (ref "X2.01") (pin "1") (pinfunction "1_1") (pintype "passive"))
    )
    (net (code "3") (name "+5V") (class "Default")
      (node (ref "R1.05") (pin "1") (pinfunction "1_1") (pintype "passive"))
      (node (ref "R1.06") (pin "2") (pinfunction "2_2") (pintype "passive"))
      (node (ref "R2.02") (pin "2") (pinfunction "2_2") (pintype "passive"))
      (node (ref "R6.03") (pin "1") (pinfunction "1_1") (pintype "passive"))
      (node (ref "R7.06") (pin "1") (pinfunction "1_1") (pintype "passive"))
      (node (ref "R7.13") (pin "2") (pinfunction "2_2") (pintype "passive"))
      (node (ref "U2.0") (pin "18") (pinfunction "IN_18") (pintype "bidirectional"))
      (node (ref "U2.0") (pin "19") (pinfunction "IN_19") (pintype "bidirectional"))
      (node (ref "X7.04") (pin "1") (pinfunction "1_1") (pintype "passive"))
      (node (ref "X7.09") (pin "3") (pinfunction "3_3") (pintype "passive"))
      (node (ref "X7.10") (pin "3") (pinfunction "3_3") (pintype "passive"))
    )
    (net (code "4") (name "+12V") (class "Default")
      (node (ref "C4.03") (pin "1") (pinfunction "1_1") (pintype "passive"))
      (node (ref "D1.01") (pin "C") (pinfunction "C_C") (pintype "passive"))
      (node (ref "F1.01") (pin "1") (pinfunction "1_1") (pintype "passive"))
      (node (ref "L4.01") (pin "2") (pinfunction "2_2") (pintype "passive"))
      (node (ref "R7.02") (pin "1") (pinfunction "1_1") (pintype "passive"))
      (node (ref "R7.07") (pin "1") (pinfunction "1_1") (pintype "passive"))
      (node (ref "R7.15") (pin "2") (pinfunction "2_2") (pintype "passive"))
    )
    (net (code "5") (name "CAR.AUXILLARY") (class "Default")
      (node (ref "U7.2") (pin "2") (pinfunction "G_2") (pintype "passive"))
      (node (ref "X7.02") (pin "IO.1") (pinfunction "IO.1_IO.1") (pintype "bidirectional"))
    )
    (net (code "6") (name "CAR.BLIGHT") (class "Default")
      (node (ref "U7.2") (pin "5") (pinfunction "G_5") (pintype "passive"))
      (node (ref "X7.02") (pin "IO.5") (pinfunction "IO.5_IO.5") (pintype "bidirectional"))
    )
    (net (code "7") (name "CAR.FLIGHT") (class "Default")
      (node (ref "U7.01") (pin "2") (pinfunction "G_2") (pintype "passive"))
      (node (ref "X7.02") (pin "IO.6") (pinfunction "IO.6_IO.6") (pintype "bidirectional"))
    )
    (net (code "8") (name "CAR.GATECTLR") (class "Default")
      (node (ref "U7.01") (pin "5") (pinfunction "G_5") (pintype "passive"))
      (node (ref "X7.02") (pin "IO.9") (pinfunction "IO.9_IO.9") (pintype "bidirectional"))
    )
    (net (code "9") (name "CAR.LAPCNT") (class "Default")
      (node (ref "X7.02") (pin "IO.7") (pinfunction "IO.7_IO.7") (pintype "bidirectional"))
      (node (ref "X7.07") (pin "1") (pinfunction "1_1") (pintype "passive"))
    )
    (net (code "10") (name "CAR.SPEED") (class "Default")
      (node (ref "X7.02") (pin "IO.8") (pinfunction "IO.8_IO.8") (pintype "bidirectional"))
      (node (ref "X7.07") (pin "2") (pinfunction "2_2") (pintype "passive"))
    )
    (net (code "11") (name "GND") (class "Default")
      (node (ref "C1.01") (pin "2") (pinfunction "2_2") (pintype "passive"))
      (node (ref "C1.02") (pin "2") (pinfunction "2_2") (pintype "passive"))
      (node (ref "C1.05") (pin "2") (pinfunction "2_2") (pintype "passive"))
      (node (ref "C1.06") (pin "2") (pinfunction "2_2") (pintype "passive"))
      (node (ref "C2.01") (pin "2") (pinfunction "2_2") (pintype "passive"))
      (node (ref "C2.02") (pin "2") (pinfunction "2_2") (pintype "passive"))
      (node (ref "C2.04") (pin "2") (pinfunction "2_2") (pintype "passive"))
      (node (ref "C2.05") (pin "-") (pinfunction "-_-") (pintype "passive"))
      (node (ref "C3.01") (pin "2") (pinfunction "2_2") (pintype "passive"))
      (node (ref "C3.02") (pin "2") (pinfunction "2_2") (pintype "passive"))
      (node (ref "C3.03") (pin "2") (pinfunction "2_2") (pintype "passive"))
      (node (ref "C3.04") (pin "2") (pinfunction "2_2") (pintype "passive"))
      (node (ref "C3.05") (pin "2") (pinfunction "2_2") (pintype "passive"))
      (node (ref "C4.01") (pin "-") (pinfunction "-_-") (pintype "passive"))
      (node (ref "C4.02") (pin "2") (pinfunction "2_2") (pintype "passive"))
      (node (ref "C4.03") (pin "2") (pinfunction "2_2") (pintype "passive"))
      (node (ref "C4.05") (pin "2") (pinfunction "2_2") (pintype "passive"))
      (node (ref "C6.01") (pin "2") (pinfunction "2_2") (pintype "passive"))
      (node (ref "C6.02") (pin "2") (pinfunction "2_2") (pintype "passive"))
      (node (ref "C6.03") (pin "2") (pinfunction "2_2") (pintype "passive"))
      (node (ref "C6.04") (pin "N") (pinfunction "-_N") (pintype "passive"))
      (node (ref "C6.05") (pin "N") (pinfunction "-_N") (pintype "passive"))
      (node (ref "D7.05") (pin "C") (pinfunction "C_C") (pintype "passive"))
      (node (ref "D7.06") (pin "C") (pinfunction "C_C") (pintype "passive"))
      (node (ref "D7.07") (pin "C") (pinfunction "C_C") (pintype "passive"))
      (node (ref "IC3.01") (pin "14") (pinfunction "RES_14") (pintype "bidirectional"))
      (node (ref "IC3.01") (pin "15") (pinfunction "RES_15") (pintype "bidirectional"))
      (node (ref "IC3.01") (pin "16") (pinfunction "RES_16") (pintype "bidirectional"))
      (node (ref "IC3.01") (pin "17") (pinfunction "RES_17") (pintype "bidirectional"))
      (node (ref "IC3.01") (pin "18") (pinfunction "RES_18") (pintype "bidirectional"))
      (node (ref "IC3.01") (pin "19") (pinfunction "GND_19") (pintype "bidirectional"))
      (node (ref "IC3.01") (pin "20") (pinfunction "GND_20") (pintype "bidirectional"))
      (node (ref "J4.01") (pin "1") (pinfunction "1_1") (pintype "passive"))
      (node (ref "NTC-") (pin "1") (pinfunction "P_1") (pintype "passive"))
      (node (ref "PAD3") (pin "1") (pinfunction "P_1") (pintype "passive"))
      (node (ref "R1.02") (pin "1") (pinfunction "1_1") (pintype "passive"))
      (node (ref "R1.04") (pin "1") (pinfunction "1_1") (pintype "passive"))
      (node (ref "R2.01") (pin "1") (pinfunction "1_1") (pintype "passive"))
      (node (ref "R2.03") (pin "1") (pinfunction "1_1") (pintype "passive"))
      (node (ref "R2.05") (pin "2") (pinfunction "2_2") (pintype "passive"))
      (node (ref "R2.08") (pin "2") (pinfunction "2_2") (pintype "passive"))
      (node (ref "R2.11") (pin "1") (pinfunction "1_1") (pintype "passive"))
      (node (ref "R2.13") (pin "1") (pinfunction "1_1") (pintype "passive"))
      (node (ref "R2.15") (pin "1") (pinfunction "1_1") (pintype "passive"))
      (node (ref "R213") (pin "2") (pinfunction "2_2") (pintype "passive"))
      (node (ref "R3.02") (pin "1") (pinfunction "1_1") (pintype "passive"))
      (node (ref "R3.04") (pin "1") (pinfunction "1_1") (pintype "passive"))
      (node (ref "R3.06") (pin "1") (pinfunction "1_1") (pintype "passive"))
      (node (ref "R4.03") (pin "1") (pinfunction "1_1") (pintype "passive"))
      (node (ref "R4.04") (pin "1") (pinfunction "1_1") (pintype "passive"))
      (node (ref "R4.05") (pin "1") (pinfunction "1_1") (pintype "passive"))
      (node (ref "R6.01") (pin "1") (pinfunction "1_1") (pintype "passive"))
      (node (ref "R7.03") (pin "2") (pinfunction "2_2") (pintype "passive"))
      (node (ref "R7.11") (pin "2") (pinfunction "2_2") (pintype "passive"))
      (node (ref "R7.12") (pin "2") (pinfunction "2_2") (pintype "passive"))
      (node (ref "U1.01") (pin "4") (pinfunction "GND_4") (pintype "bidirectional"))
      (node (ref "U1.01") (pin "PAD") (pinfunction "PAD_PAD") (pintype "bidirectional"))
      (node (ref "U2.0") (pin "20") (pinfunction "AGND_20") (pintype "bidirectional"))
      (node (ref "U2.0") (pin "21") (pinfunction "PGND_21") (pintype "bidirectional"))
      (node (ref "U2.0") (pin "22") (pinfunction "PGND_22") (pintype "bidirectional"))
      (node (ref "U2.0") (pin "PAD") (pinfunction "THERMAL_PAD") (pintype "bidirectional"))
      (node (ref "U4.01") (pin "1") (pinfunction "GND_1") (pintype "bidirectional"))
      (node (ref "U4.01") (pin "7") (pinfunction "PGND_7") (pintype "bidirectional"))
      (node (ref "U4.01") (pin "THERMAL") (pinfunction "PAD_THERMAL") (pintype "bidirectional"))
      (node (ref "U6.01") (pin "11") (pinfunction "GND_11") (pintype "passive"))
      (node (ref "U6.01") (pin "3") (pinfunction "PGND_3") (pintype "passive"))
      (node (ref "U6.01") (pin "4") (pinfunction "PGND_2_4") (pintype "passive"))
      (node (ref "U6.01") (pin "5") (pinfunction "PGND_3_5") (pintype "passive"))
      (node (ref "U6.01") (pin "PAD") (pinfunction "EP_PAD") (pintype "passive"))
      (node (ref "U7.01") (pin "1") (pinfunction "S_1") (pintype "passive"))
      (node (ref "U7.01") (pin "4") (pinfunction "S_4") (pintype "passive"))
      (node (ref "U7.03") (pin "1") (pinfunction "S_1") (pintype "passive"))
      (node (ref "U7.03") (pin "4") (pinfunction "S_4") (pintype "passive"))
      (node (ref "U7.2") (pin "1") (pinfunction "S_1") (pintype "passive"))
      (node (ref "U7.2") (pin "4") (pinfunction "S_4") (pintype "passive"))
      (node (ref "X2.01") (pin "2") (pinfunction "2_2") (pintype "passive"))
      (node (ref "X7.02") (pin "GND.1") (pinfunction "GND_GND.1") (pintype "bidirectional"))
      (node (ref "X7.02") (pin "GND2") (pinfunction "GND_GND2") (pintype "bidirectional"))
      (node (ref "X7.02") (pin "GND3") (pinfunction "GND_GND3") (pintype "bidirectional"))
      (node (ref "X7.07") (pin "3") (pinfunction "3_3") (pintype "passive"))
      (node (ref "X7.07") (pin "4") (pinfunction "4_4") (pintype "passive"))
    )
    (net (code "12") (name "GND.RAIL") (class "Default")
      (node (ref "R7.12") (pin "1") (pinfunction "1_1") (pintype "passive"))
      (node (ref "X7.01") (pin "1") (pinfunction "1_1") (pintype "passive"))
    )
    (net (code "13") (name "GYRO.SCL") (class "Default")
      (node (ref "IC3.01") (pin "2") (pinfunction "SCL/SPC_2") (pintype "bidirectional"))
      (node (ref "PAD2") (pin "1") (pinfunction "P_1") (pintype "passive"))
      (node (ref "R7.17") (pin "1") (pinfunction "1_1") (pintype "passive"))
      (node (ref "R7.19") (pin "1") (pinfunction "1_1") (pintype "passive"))
    )
    (net (code "14") (name "GYRO.SDA") (class "Default")
      (node (ref "IC3.01") (pin "4") (pinfunction "SDA/SDI/SDO_4") (pintype "bidirectional"))
      (node (ref "PAD1") (pin "1") (pinfunction "P_1") (pintype "passive"))
      (node (ref "R7.18") (pin "1") (pinfunction "1_1") (pintype "passive"))
      (node (ref "R7.20") (pin "1") (pinfunction "1_1") (pintype "passive"))
    )
    (net (code "15") (name "IC2.0.~{CHG}") (class "Default")
      (node (ref "U2.0") (pin "13") (pinfunction "~{CHG}_13") (pintype "bidirectional"))
      (node (ref "U7.03") (pin "2") (pinfunction "G_2") (pintype "passive"))
    )
    (net (code "16") (name "IC2.0.~{PG}") (class "Default")
      (node (ref "U2.0") (pin "10") (pinfunction "~{PG}_10") (pintype "bidirectional"))
      (node (ref "U7.03") (pin "5") (pinfunction "G_5") (pintype "passive"))
    )
    (net (code "17") (name "LBO") (class "Default")
      (node (ref "R6.04") (pin "1") (pinfunction "1_1") (pintype "passive"))
      (node (ref "U6.01") (pin "10") (pinfunction "LBO_10") (pintype "output"))
      (node (ref "X7.02") (pin "ADC.0") (pinfunction "ADC.0_ADC.0") (pintype "bidirectional"))
    )
    (net (code "18") (name "MOT.IN1") (class "Default")
      (node (ref "R4.05") (pin "2") (pinfunction "2_2") (pintype "passive"))
      (node (ref "U4.01") (pin "3") (pinfunction "IN1_3") (pintype "bidirectional"))
      (node (ref "X7.02") (pin "IO.3") (pinfunction "IO.3_IO.3") (pintype "bidirectional"))
    )
    (net (code "19") (name "MOT.IN2") (class "Default")
      (node (ref "R4.04") (pin "2") (pinfunction "2_2") (pintype "passive"))
      (node (ref "U4.01") (pin "2") (pinfunction "IN2_2") (pintype "bidirectional"))
      (node (ref "X7.02") (pin "IO.4") (pinfunction "IO.4_IO.4") (pintype "bidirectional"))
    )
    (net (code "20") (name "Net-(C1.04-Pad2)") (class "Default")
      (node (ref "C1.04") (pin "2") (pinfunction "2_2") (pintype "passive"))
      (node (ref "R1.02") (pin "2") (pinfunction "2_2") (pintype "passive"))
    )
    (net (code "21") (name "Net-(C1.05-Pad1)") (class "Default")
      (node (ref "C1.05") (pin "1") (pinfunction "1_1") (pintype "passive"))
      (node (ref "C1.06") (pin "1") (pinfunction "1_1") (pintype "passive"))
      (node (ref "L1.02") (pin "1") (pinfunction "1_1") (pintype "passive"))
      (node (ref "L1.03") (pin "1") (pinfunction "1_1") (pintype "passive"))
      (node (ref "R1.03") (pin "2") (pinfunction "2_2") (pintype "passive"))
    )
    (net (code "22") (name "Net-(C2.03-Pad1)") (class "Default")
      (node (ref "C2.03") (pin "1") (pinfunction "1_1") (pintype "passive"))
      (node (ref "L2.01") (pin "2") (pinfunction "2_2") (pintype "passive"))
      (node (ref "U2.0") (pin "23") (pinfunction "SW_23") (pintype "bidirectional"))
      (node (ref "U2.0") (pin "24") (pinfunction "SW_24") (pintype "bidirectional"))
    )
    (net (code "23") (name "Net-(C2.04-Pad1)") (class "Default")
      (node (ref "C2.04") (pin "1") (pinfunction "1_1") (pintype "passive"))
      (node (ref "L2.01") (pin "1") (pinfunction "1_1") (pintype "passive"))
      (node (ref "L2.02") (pin "1") (pinfunction "1_1") (pintype "passive"))
      (node (ref "Q2.01") (pin "1") (pinfunction "S_1") (pintype "passive"))
      (node (ref "Q2.01") (pin "2") (pinfunction "S_2") (pintype "passive"))
      (node (ref "Q2.01") (pin "3") (pinfunction "S_3") (pintype "passive"))
      (node (ref "U2.0") (pin "6") (pinfunction "SYS_6") (pintype "bidirectional"))
      (node (ref "U2.0") (pin "7") (pinfunction "SYS_7") (pintype "bidirectional"))
    )
    (net (code "24") (name "Net-(C6.04-+)") (class "Default")
      (node (ref "C6.03") (pin "1") (pinfunction "1_1") (pintype "passive"))
      (node (ref "C6.04") (pin "P") (pinfunction "+_P") (pintype "passive"))
      (node (ref "C6.05") (pin "P") (pinfunction "+_P") (pintype "passive"))
      (node (ref "L6.02") (pin "1") (pinfunction "1_1") (pintype "passive"))
      (node (ref "U6.01") (pin "13") (pinfunction "VOUT_13") (pintype "output"))
      (node (ref "U6.01") (pin "14") (pinfunction "VOUT_2_14") (pintype "output"))
      (node (ref "U6.01") (pin "15") (pinfunction "VOUT_3_15") (pintype "output"))
    )
    (net (code "25") (name "Net-(D7.03-PadA)") (class "Default")
      (node (ref "D7.03") (pin "A") (pinfunction "A_A") (pintype "passive"))
      (node (ref "R7.16") (pin "1") (pinfunction "1_1") (pintype "passive"))
    )
    (net (code "26") (name "Net-(D7.04-PadA)") (class "Default")
      (node (ref "D7.04") (pin "A") (pinfunction "A_A") (pintype "passive"))
      (node (ref "R7.01") (pin "1") (pinfunction "1_1") (pintype "passive"))
    )
    (net (code "27") (name "Net-(D7.05-PadA)") (class "Default")
      (node (ref "D7.05") (pin "A") (pinfunction "A_A") (pintype "passive"))
      (node (ref "R7.13") (pin "1") (pinfunction "1_1") (pintype "passive"))
    )
    (net (code "28") (name "Net-(D7.06-PadA)") (class "Default")
      (node (ref "D7.06") (pin "A") (pinfunction "A_A") (pintype "passive"))
      (node (ref "R7.14") (pin "1") (pinfunction "1_1") (pintype "passive"))
    )
    (net (code "29") (name "Net-(D7.07-PadA)") (class "Default")
      (node (ref "D7.07") (pin "A") (pinfunction "A_A") (pintype "passive"))
      (node (ref "R7.15") (pin "1") (pinfunction "1_1") (pintype "passive"))
    )
    (net (code "30") (name "Net-(F1.01-Pad2)") (class "Default")
      (node (ref "F1.01") (pin "2") (pinfunction "2_2") (pintype "passive"))
      (node (ref "L1.01") (pin "1") (pinfunction "1_1") (pintype "passive"))
    )
    (net (code "31") (name "Net-(IC3.01-C1)") (class "Default")
      (node (ref "C3.02") (pin "1") (pinfunction "1_1") (pintype "passive"))
      (node (ref "IC3.01") (pin "24") (pinfunction "C1_24") (pintype "bidirectional"))
    )
    (net (code "32") (name "Net-(IC3.01-CAP)") (class "Default")
      (node (ref "C3.01") (pin "1") (pinfunction "1_1") (pintype "passive"))
      (node (ref "IC3.01") (pin "21") (pinfunction "CAP_21") (pintype "bidirectional"))
    )
    (net (code "33") (name "Net-(IC3.01-CS_A{slash}G)") (class "Default")
      (node (ref "IC3.01") (pin "7") (pinfunction "CS_A/G_7") (pintype "bidirectional"))
      (node (ref "R3.07") (pin "1") (pinfunction "1_1") (pintype "passive"))
    )
    (net (code "34") (name "Net-(IC3.01-CS_M)") (class "Default")
      (node (ref "IC3.01") (pin "8") (pinfunction "CS_M_8") (pintype "bidirectional"))
      (node (ref "R3.08") (pin "1") (pinfunction "1_1") (pintype "passive"))
    )
    (net (code "35") (name "Net-(IC3.01-DEN_A{slash}G)") (class "Default")
      (node (ref "IC3.01") (pin "13") (pinfunction "DEN_A/G_13") (pintype "bidirectional"))
      (node (ref "R3.01") (pin "1") (pinfunction "1_1") (pintype "passive"))
      (node (ref "R3.02") (pin "2") (pinfunction "2_2") (pintype "passive"))
    )
    (net (code "36") (name "Net-(IC3.01-SDO_A{slash}G)") (class "Default")
      (node (ref "IC3.01") (pin "5") (pinfunction "SDO_A/G_5") (pintype "bidirectional"))
      (node (ref "R3.03") (pin "1") (pinfunction "1_1") (pintype "passive"))
      (node (ref "R3.04") (pin "2") (pinfunction "2_2") (pintype "passive"))
    )
    (net (code "37") (name "Net-(IC3.01-SDO_M)") (class "Default")
      (node (ref "IC3.01") (pin "6") (pinfunction "SDO_M_6") (pintype "bidirectional"))
      (node (ref "R3.05") (pin "1") (pinfunction "1_1") (pintype "passive"))
      (node (ref "R3.06") (pin "2") (pinfunction "2_2") (pintype "passive"))
    )
    (net (code "38") (name "Net-(L1.03-Pad2)") (class "Default")
      (node (ref "L1.03") (pin "2") (pinfunction "2_2") (pintype "passive"))
      (node (ref "R1.05") (pin "2") (pinfunction "2_2") (pintype "passive"))
      (node (ref "R1.06") (pin "1") (pinfunction "1_1") (pintype "passive"))
    )
    (net (code "39") (name "Net-(L2.02-Pad2)") (class "Default")
      (node (ref "L2.02") (pin "2") (pinfunction "2_2") (pintype "passive"))
      (node (ref "R2.07") (pin "2") (pinfunction "2_2") (pintype "passive"))
    )
    (net (code "40") (name "Net-(L6.02-Pad2)") (class "Default")
      (node (ref "L6.02") (pin "2") (pinfunction "2_2") (pintype "passive"))
      (node (ref "R6.03") (pin "2") (pinfunction "2_2") (pintype "passive"))
    )
    (net (code "41") (name "Net-(NTC+-P)") (class "Default")
      (node (ref "NTC+") (pin "1") (pinfunction "P_1") (pintype "passive"))
      (node (ref "R2.04") (pin "2") (pinfunction "2_2") (pintype "passive"))
      (node (ref "R2.05") (pin "1") (pinfunction "1_1") (pintype "passive"))
      (node (ref "R2.08") (pin "1") (pinfunction "1_1") (pintype "passive"))
      (node (ref "U2.0") (pin "5") (pinfunction "TS_5") (pintype "bidirectional"))
    )
    (net (code "42") (name "Net-(Q2.01-G)") (class "Default")
      (node (ref "Q2.01") (pin "4") (pinfunction "G_4") (pintype "passive"))
      (node (ref "U2.0") (pin "11") (pinfunction "BGATE_11") (pintype "bidirectional"))
    )
    (net (code "43") (name "Net-(R2.10-Pad1)") (class "Default")
      (node (ref "R2.10") (pin "1") (pinfunction "1_1") (pintype "passive"))
      (node (ref "R2.11") (pin "2") (pinfunction "2_2") (pintype "passive"))
      (node (ref "U2.0") (pin "17") (pinfunction "IUSB_17") (pintype "bidirectional"))
    )
    (net (code "44") (name "Net-(R2.12-Pad1)") (class "Default")
      (node (ref "R2.12") (pin "1") (pinfunction "1_1") (pintype "passive"))
      (node (ref "R2.13") (pin "2") (pinfunction "2_2") (pintype "passive"))
      (node (ref "U2.0") (pin "16") (pinfunction "IUSB_16") (pintype "bidirectional"))
    )
    (net (code "45") (name "Net-(R2.14-Pad1)") (class "Default")
      (node (ref "R2.14") (pin "1") (pinfunction "1_1") (pintype "passive"))
      (node (ref "R2.15") (pin "2") (pinfunction "2_2") (pintype "passive"))
      (node (ref "U2.0") (pin "14") (pinfunction "IUSB_14") (pintype "bidirectional"))
    )
    (net (code "46") (name "Net-(R7.04-Pad2)") (class "Default")
      (node (ref "R7.04") (pin "2") (pinfunction "2_2") (pintype "passive"))
      (node (ref "X7.08") (pin "1") (pinfunction "1_1") (pintype "bidirectional"))
    )
    (net (code "47") (name "Net-(R7.06-Pad2)") (class "Default")
      (node (ref "R7.06") (pin "2") (pinfunction "2_2") (pintype "passive"))
      (node (ref "X7.02") (pin "5V") (pinfunction "5V_5V") (pintype "bidirectional"))
    )
    (net (code "48") (name "Net-(R7.07-Pad2)") (class "Default")
      (node (ref "R7.07") (pin "2") (pinfunction "2_2") (pintype "passive"))
      (node (ref "X7.02") (pin "VIN") (pinfunction "VIN_VIN") (pintype "bidirectional"))
    )
    (net (code "49") (name "Net-(R7.08-Pad2)") (class "Default")
      (node (ref "R7.08") (pin "2") (pinfunction "2_2") (pintype "passive"))
      (node (ref "X7.11") (pin "2") (pinfunction "2_2") (pintype "bidirectional"))
    )
    (net (code "50") (name "Net-(R7.09-Pad2)") (class "Default")
      (node (ref "R7.09") (pin "2") (pinfunction "2_2") (pintype "passive"))
      (node (ref "X7.06") (pin "1") (pinfunction "1_1") (pintype "bidirectional"))
    )
    (net (code "51") (name "Net-(R7.10-Pad2)") (class "Default")
      (node (ref "R7.10") (pin "2") (pinfunction "2_2") (pintype "passive"))
      (node (ref "X7.03") (pin "2") (pinfunction "2_2") (pintype "bidirectional"))
    )
    (net (code "52") (name "Net-(R7.19-Pad2)") (class "Default")
      (node (ref "R7.19") (pin "2") (pinfunction "2_2") (pintype "passive"))
      (node (ref "X7.02") (pin "SDA") (pinfunction "SDA_SDA") (pintype "bidirectional"))
    )
    (net (code "53") (name "Net-(R7.20-Pad2)") (class "Default")
      (node (ref "R7.20") (pin "2") (pinfunction "2_2") (pintype "passive"))
      (node (ref "X7.02") (pin "SCL") (pinfunction "SCL_SCL") (pintype "bidirectional"))
    )
    (net (code "54") (name "Net-(U1.01-BOOT)") (class "Default")
      (node (ref "C1.03") (pin "1") (pinfunction "1_1") (pintype "passive"))
      (node (ref "U1.01") (pin "1") (pinfunction "BOOT_1") (pintype "bidirectional"))
    )
    (net (code "55") (name "Net-(U1.01-COMP)") (class "Default")
      (node (ref "C1.04") (pin "1") (pinfunction "1_1") (pintype "passive"))
      (node (ref "U1.01") (pin "6") (pinfunction "COMP_6") (pintype "bidirectional"))
    )
    (net (code "56") (name "Net-(U1.01-EN)") (class "Default")
      (node (ref "R1.01") (pin "2") (pinfunction "2_2") (pintype "passive"))
      (node (ref "U1.01") (pin "7") (pinfunction "EN_7") (pintype "bidirectional"))
    )
    (net (code "57") (name "Net-(U1.01-FB)") (class "Default")
      (node (ref "R1.03") (pin "1") (pinfunction "1_1") (pintype "passive"))
      (node (ref "R1.04") (pin "2") (pinfunction "2_2") (pintype "passive"))
      (node (ref "U1.01") (pin "5") (pinfunction "FB_5") (pintype "bidirectional"))
    )
    (net (code "58") (name "Net-(U1.01-SS)") (class "Default")
      (node (ref "C1.02") (pin "1") (pinfunction "1_1") (pintype "passive"))
      (node (ref "U1.01") (pin "8") (pinfunction "SS_8") (pintype "bidirectional"))
    )
    (net (code "59") (name "Net-(U1.01-SW)") (class "Default")
      (node (ref "C1.03") (pin "2") (pinfunction "2_2") (pintype "passive"))
      (node (ref "L1.02") (pin "2") (pinfunction "2_2") (pintype "passive"))
      (node (ref "U1.01") (pin "3") (pinfunction "SW_3") (pintype "bidirectional"))
    )
    (net (code "60") (name "Net-(U1.01-VIN)") (class "Default")
      (node (ref "C1.01") (pin "1") (pinfunction "1_1") (pintype "passive"))
      (node (ref "L1.01") (pin "2") (pinfunction "2_2") (pintype "passive"))
      (node (ref "R1.01") (pin "1") (pinfunction "1_1") (pintype "passive"))
      (node (ref "U1.01") (pin "2") (pinfunction "VIN_2") (pintype "bidirectional"))
    )
    (net (code "61") (name "Net-(U2.0B-BOOT)") (class "Default")
      (node (ref "C2.03") (pin "2") (pinfunction "2_2") (pintype "passive"))
      (node (ref "U2.0") (pin "2") (pinfunction "BOOT_2") (pintype "bidirectional"))
    )
    (net (code "62") (name "Net-(U2.0B-ISET)") (class "Default")
      (node (ref "R2.03") (pin "2") (pinfunction "2_2") (pintype "passive"))
      (node (ref "U2.0") (pin "12") (pinfunction "ISET_12") (pintype "bidirectional"))
    )
    (net (code "63") (name "Net-(U2.0B-PMID)") (class "Default")
      (node (ref "C2.01") (pin "1") (pinfunction "1_1") (pintype "passive"))
      (node (ref "U2.0") (pin "1") (pinfunction "PMID_1") (pintype "bidirectional"))
    )
    (net (code "64") (name "Net-(U2.0B-VDPM)") (class "Default")
      (node (ref "R2.01") (pin "2") (pinfunction "2_2") (pintype "passive"))
      (node (ref "R2.02") (pin "1") (pinfunction "1_1") (pintype "passive"))
      (node (ref "U2.0") (pin "15") (pinfunction "VDPM_15") (pintype "bidirectional"))
    )
    (net (code "65") (name "Net-(U2.0B-~{CE})") (class "Default")
      (node (ref "R213") (pin "1") (pinfunction "1_1") (pintype "passive"))
      (node (ref "U2.0") (pin "4") (pinfunction "~{CE}_4") (pintype "bidirectional"))
    )
    (net (code "66") (name "Net-(U4.01-ILIM)") (class "Default")
      (node (ref "R4.03") (pin "2") (pinfunction "2_2") (pintype "passive"))
      (node (ref "U4.01") (pin "4") (pinfunction "ILIM_4") (pintype "bidirectional"))
    )
    (net (code "67") (name "Net-(U4.01-OUT1)") (class "Default")
      (node (ref "C4.04") (pin "2") (pinfunction "2_2") (pintype "passive"))
      (node (ref "C4.05") (pin "1") (pinfunction "1_1") (pintype "passive"))
      (node (ref "U4.01") (pin "6") (pinfunction "OUT1_6") (pintype "bidirectional"))
      (node (ref "X7.05") (pin "1") (pinfunction "1_1") (pintype "passive"))
    )
    (net (code "68") (name "Net-(U4.01-OUT2)") (class "Default")
      (node (ref "J4.01") (pin "3") (pinfunction "3_3") (pintype "passive"))
      (node (ref "U4.01") (pin "8") (pinfunction "OUT2_8") (pintype "bidirectional"))
    )
    (net (code "69") (name "Net-(U4.01-VM)") (class "Default")
      (node (ref "C4.01") (pin "+") (pinfunction "+_+") (pintype "passive"))
      (node (ref "C4.02") (pin "1") (pinfunction "1_1") (pintype "passive"))
      (node (ref "C4.04") (pin "1") (pinfunction "1_1") (pintype "passive"))
      (node (ref "L4.01") (pin "1") (pinfunction "1_1") (pintype "passive"))
      (node (ref "U4.01") (pin "5") (pinfunction "VM_5") (pintype "bidirectional"))
    )
    (net (code "70") (name "Net-(U6.01-EN)") (class "Default")
      (node (ref "R6.05") (pin "1") (pinfunction "1_1") (pintype "passive"))
      (node (ref "U6.01") (pin "9") (pinfunction "EN_9") (pintype "input"))
    )
    (net (code "71") (name "Net-(U6.01-LBI)") (class "Default")
      (node (ref "R6.01") (pin "2") (pinfunction "2_2") (pintype "passive"))
      (node (ref "U6.01") (pin "7") (pinfunction "LBI_7") (pintype "input"))
    )
    (net (code "72") (name "Net-(U6.01-SW)") (class "Default")
      (node (ref "L6.01") (pin "2") (pinfunction "2_2") (pintype "passive"))
      (node (ref "U6.01") (pin "1") (pinfunction "SW_1") (pintype "input"))
      (node (ref "U6.01") (pin "2") (pinfunction "SW_2_2") (pintype "input"))
    )
    (net (code "73") (name "Net-(U6.01-SYNC)") (class "Default")
      (node (ref "R6.02") (pin "2") (pinfunction "2_2") (pintype "passive"))
      (node (ref "U6.01") (pin "8") (pinfunction "SYNC_8") (pintype "input"))
    )
    (net (code "74") (name "Net-(U7.01A-D)") (class "Default")
      (node (ref "R7.04") (pin "1") (pinfunction "1_1") (pintype "passive"))
      (node (ref "U7.01") (pin "6") (pinfunction "D_6") (pintype "passive"))
    )
    (net (code "75") (name "Net-(U7.01B-D)") (class "Default")
      (node (ref "R7.08") (pin "1") (pinfunction "1_1") (pintype "passive"))
      (node (ref "U7.01") (pin "3") (pinfunction "D_3") (pintype "passive"))
    )
    (net (code "76") (name "Net-(U7.2A-D)") (class "Default")
      (node (ref "R7.10") (pin "1") (pinfunction "1_1") (pintype "passive"))
      (node (ref "U7.2") (pin "6") (pinfunction "D_6") (pintype "passive"))
    )
    (net (code "77") (name "Net-(U7.2B-D)") (class "Default")
      (node (ref "R7.09") (pin "1") (pinfunction "1_1") (pintype "passive"))
      (node (ref "U7.2") (pin "3") (pinfunction "D_3") (pintype "passive"))
    )
    (net (code "78") (name "Net-(U7.03A-D)") (class "Default")
      (node (ref "D7.03") (pin "C") (pinfunction "C_C") (pintype "passive"))
      (node (ref "U7.03") (pin "6") (pinfunction "D_6") (pintype "passive"))
    )
    (net (code "79") (name "Net-(U7.03B-D)") (class "Default")
      (node (ref "D7.04") (pin "C") (pinfunction "C_C") (pintype "passive"))
      (node (ref "U7.03") (pin "3") (pinfunction "D_3") (pintype "passive"))
    )
    (net (code "80") (name "Net-(X7.02B-3V3)") (class "Default")
      (node (ref "R7.05") (pin "2") (pinfunction "2_2") (pintype "passive"))
      (node (ref "X7.02") (pin "3.3V") (pinfunction "3V3_3.3V") (pintype "bidirectional"))
    )
    (net (code "81") (name "Net-(X7.03-Pad1)") (class "Default")
      (node (ref "X7.03") (pin "1") (pinfunction "1_1") (pintype "bidirectional"))
      (node (ref "X7.06") (pin "2") (pinfunction "2_2") (pintype "bidirectional"))
      (node (ref "X7.09") (pin "2") (pinfunction "2_2") (pintype "passive"))
    )
    (net (code "82") (name "Net-(X7.04B-1)") (class "Default")
      (node (ref "R7.11") (pin "1") (pinfunction "1_1") (pintype "passive"))
      (node (ref "X7.04") (pin "2") (pinfunction "1_2") (pintype "passive"))
    )
    (net (code "83") (name "Net-(X7.05B-1)") (class "Default")
      (node (ref "J4.01") (pin "2") (pinfunction "2_2") (pintype "passive"))
      (node (ref "X7.05") (pin "2") (pinfunction "1_2") (pintype "passive"))
    )
    (net (code "84") (name "Net-(X7.08-Pad2)") (class "Default")
      (node (ref "X7.08") (pin "2") (pinfunction "2_2") (pintype "bidirectional"))
      (node (ref "X7.10") (pin "2") (pinfunction "2_2") (pintype "passive"))
      (node (ref "X7.11") (pin "1") (pinfunction "1_1") (pintype "bidirectional"))
    )
    (net (code "85") (name "RAILS.RX") (class "Default")
      (node (ref "R7.02") (pin "2") (pinfunction "2_2") (pintype "passive"))
      (node (ref "R7.03") (pin "1") (pinfunction "1_1") (pintype "passive"))
      (node (ref "X7.02") (pin "IO.0") (pinfunction "IO.0_IO.0") (pintype "bidirectional"))
    )
    (net (code "86") (name "U2.0{slash}DRV") (class "Default")
      (node (ref "C2.02") (pin "1") (pinfunction "1_1") (pintype "passive"))
      (node (ref "R2.04") (pin "1") (pinfunction "1_1") (pintype "passive"))
      (node (ref "U2.0") (pin "3") (pinfunction "DRV_3") (pintype "bidirectional"))
    )
    (net (code "87") (name "VCC{slash}2") (class "Default")
      (node (ref "D1.01") (pin "A") (pinfunction "A_A") (pintype "passive"))
      (node (ref "X7.01") (pin "2") (pinfunction "1_2") (pintype "passive"))
    )
    (net (code "88") (name "unconnected-(IC3.01-DRDY_M-Pad9)") (class "Default")
      (node (ref "IC3.01") (pin "9") (pinfunction "DRDY_M_9") (pintype "bidirectional"))
    )
    (net (code "89") (name "unconnected-(IC3.01-INT2_A{slash}G-Pad12)") (class "Default")
      (node (ref "IC3.01") (pin "12") (pinfunction "INT2_A/G_12") (pintype "bidirectional"))
    )
    (net (code "90") (name "unconnected-(IC3.01-INT_M-Pad10)") (class "Default")
      (node (ref "IC3.01") (pin "10") (pinfunction "INT_M_10") (pintype "bidirectional"))
    )
    (net (code "91") (name "unconnected-(TP1-PadTP)") (class "Default")
      (node (ref "TP1") (pin "TP") (pinfunction "TP_TP") (pintype "input"))
    )
    (net (code "92") (name "unconnected-(TP2-PadTP)") (class "Default")
      (node (ref "TP2") (pin "TP") (pinfunction "TP_TP") (pintype "input"))
    )
    (net (code "93") (name "unconnected-(U6.01-FB-Pad12)") (class "Default")
      (node (ref "U6.01") (pin "12") (pinfunction "FB_12") (pintype "input"))
    )
    (net (code "94") (name "unconnected-(U6.01-NC-Pad16)") (class "Default")
      (node (ref "U6.01") (pin "16") (pinfunction "NC_16") (pintype "no_connect"))
    )
    (net (code "95") (name "unconnected-(X7.02-PadADC.1)") (class "Default")
      (node (ref "X7.02") (pin "ADC.1") (pinfunction "ADC.1_ADC.1") (pintype "bidirectional"))
    )
    (net (code "96") (name "unconnected-(X7.02-PadADC.2)") (class "Default")
      (node (ref "X7.02") (pin "ADC.2") (pinfunction "ADC.2_ADC.2") (pintype "bidirectional"))
    )
    (net (code "97") (name "unconnected-(X7.02-PadADC.3)") (class "Default")
      (node (ref "X7.02") (pin "ADC.3") (pinfunction "ADC.3_ADC.3") (pintype "bidirectional"))
    )
    (net (code "98") (name "unconnected-(X7.02-PadADC.4)") (class "Default")
      (node (ref "X7.02") (pin "ADC.4") (pinfunction "ADC.4_ADC.4") (pintype "bidirectional"))
    )
    (net (code "99") (name "unconnected-(X7.02-PadADC.5)") (class "Default")
      (node (ref "X7.02") (pin "ADC.5") (pinfunction "ADC.5_ADC.5") (pintype "bidirectional"))
    )
    (net (code "100") (name "unconnected-(X7.02-PadAREF)") (class "Default")
      (node (ref "X7.02") (pin "AREF") (pinfunction "AREF_AREF") (pintype "bidirectional"))
    )
    (net (code "101") (name "unconnected-(X7.02-PadIO.10)") (class "Default")
      (node (ref "X7.02") (pin "IO.10") (pinfunction "IO.10_IO.10") (pintype "bidirectional"))
    )
    (net (code "102") (name "unconnected-(X7.02-PadIO.11)") (class "Default")
      (node (ref "X7.02") (pin "IO.11") (pinfunction "IO.11_IO.11") (pintype "bidirectional"))
    )
    (net (code "103") (name "unconnected-(X7.02-PadIO.12)") (class "Default")
      (node (ref "X7.02") (pin "IO.12") (pinfunction "IO.12_IO.12") (pintype "bidirectional"))
    )
    (net (code "104") (name "unconnected-(X7.02-PadIO.13)") (class "Default")
      (node (ref "X7.02") (pin "IO.13") (pinfunction "IO.13_IO.13") (pintype "bidirectional"))
    )
    (net (code "105") (name "unconnected-(X7.02-PadN{slash}C)") (class "Default")
      (node (ref "X7.02") (pin "N/C") (pinfunction "N/C_N/C") (pintype "bidirectional"))
    )
    (net (code "106") (name "unconnected-(X7.02-PadRESET)") (class "Default")
      (node (ref "X7.02") (pin "RESET") (pinfunction "RESET_RESET") (pintype "bidirectional"))
    )
    (net (code "107") (name "unconnected-(X7.02B-IOREF-PadI{slash}OREF)") (class "Default")
      (node (ref "X7.02") (pin "I/OREF") (pinfunction "IOREF_I/OREF") (pintype "bidirectional"))
    )
    (net (code "108") (name "~{IRQ_GYRO}") (class "Default")
      (node (ref "IC3.01") (pin "11") (pinfunction "INT1_A/G_11") (pintype "bidirectional"))
      (node (ref "X7.02") (pin "IO.2") (pinfunction "IO.2_IO.2") (pintype "bidirectional"))
    )
  )
)
